# io-board-d-3.net
KiCad netlist of a schematic drawn in EAGLE
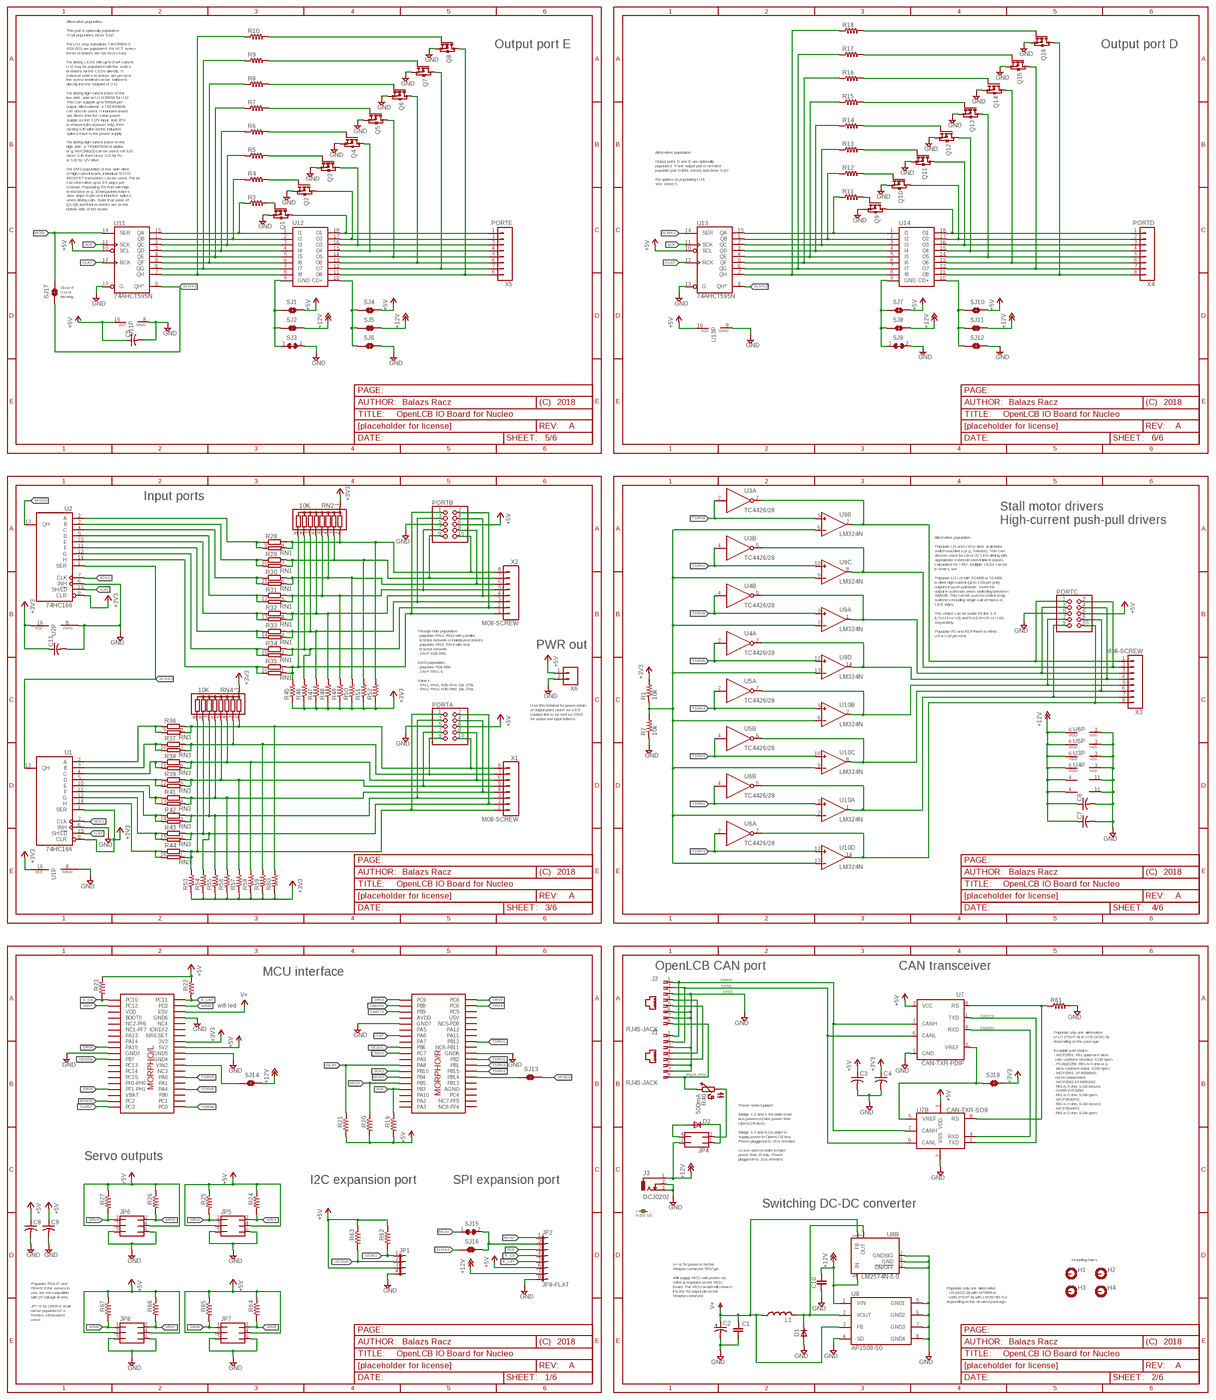
[diagram p0: schematic, sheet 1, overview]
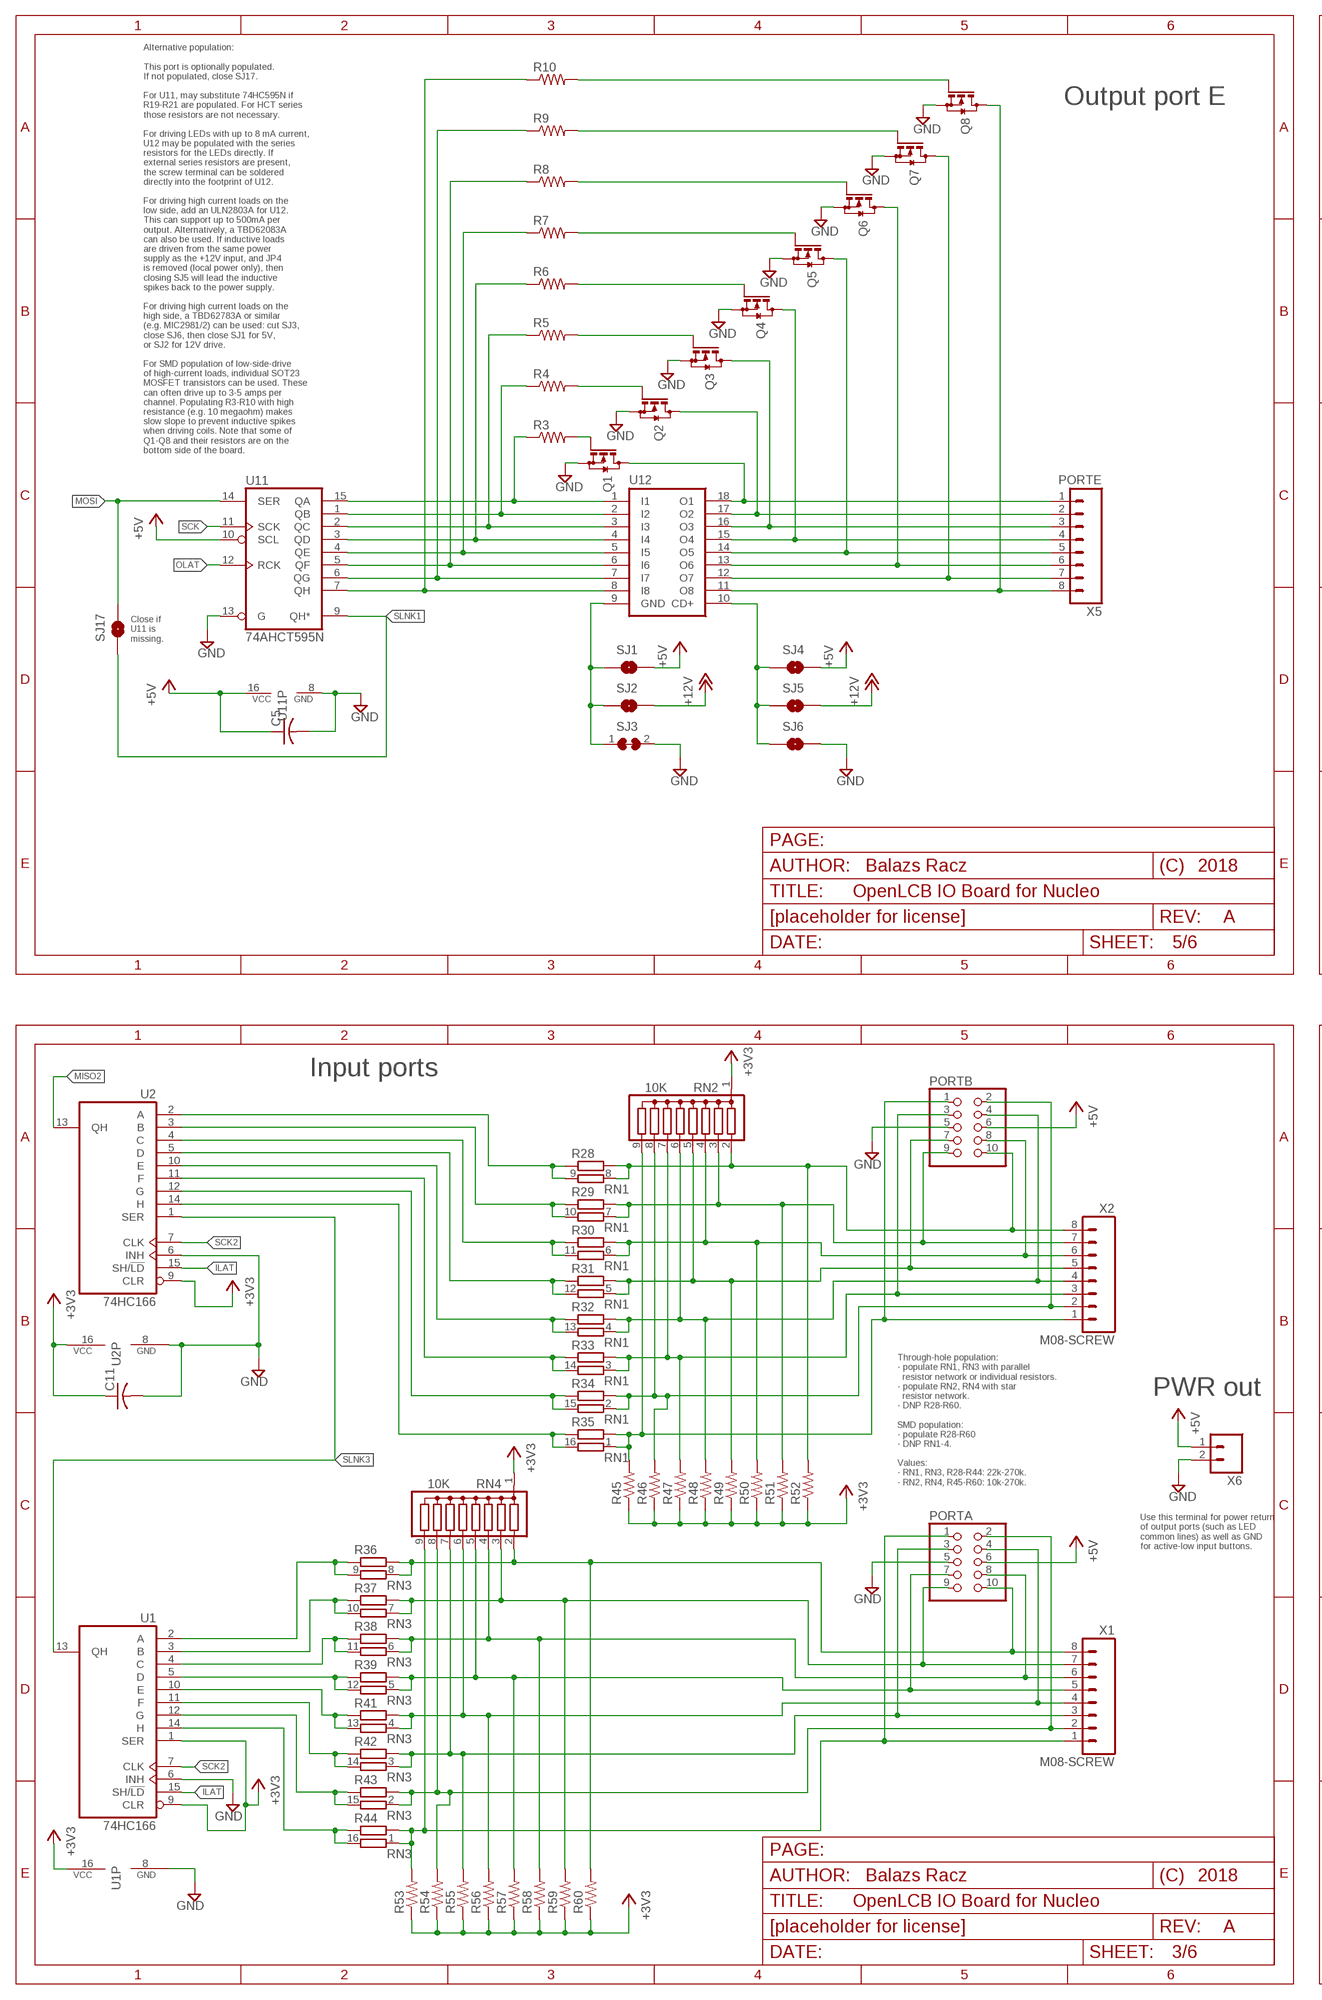
[diagram p1: schematic, sheet 1, part 1 of 4]
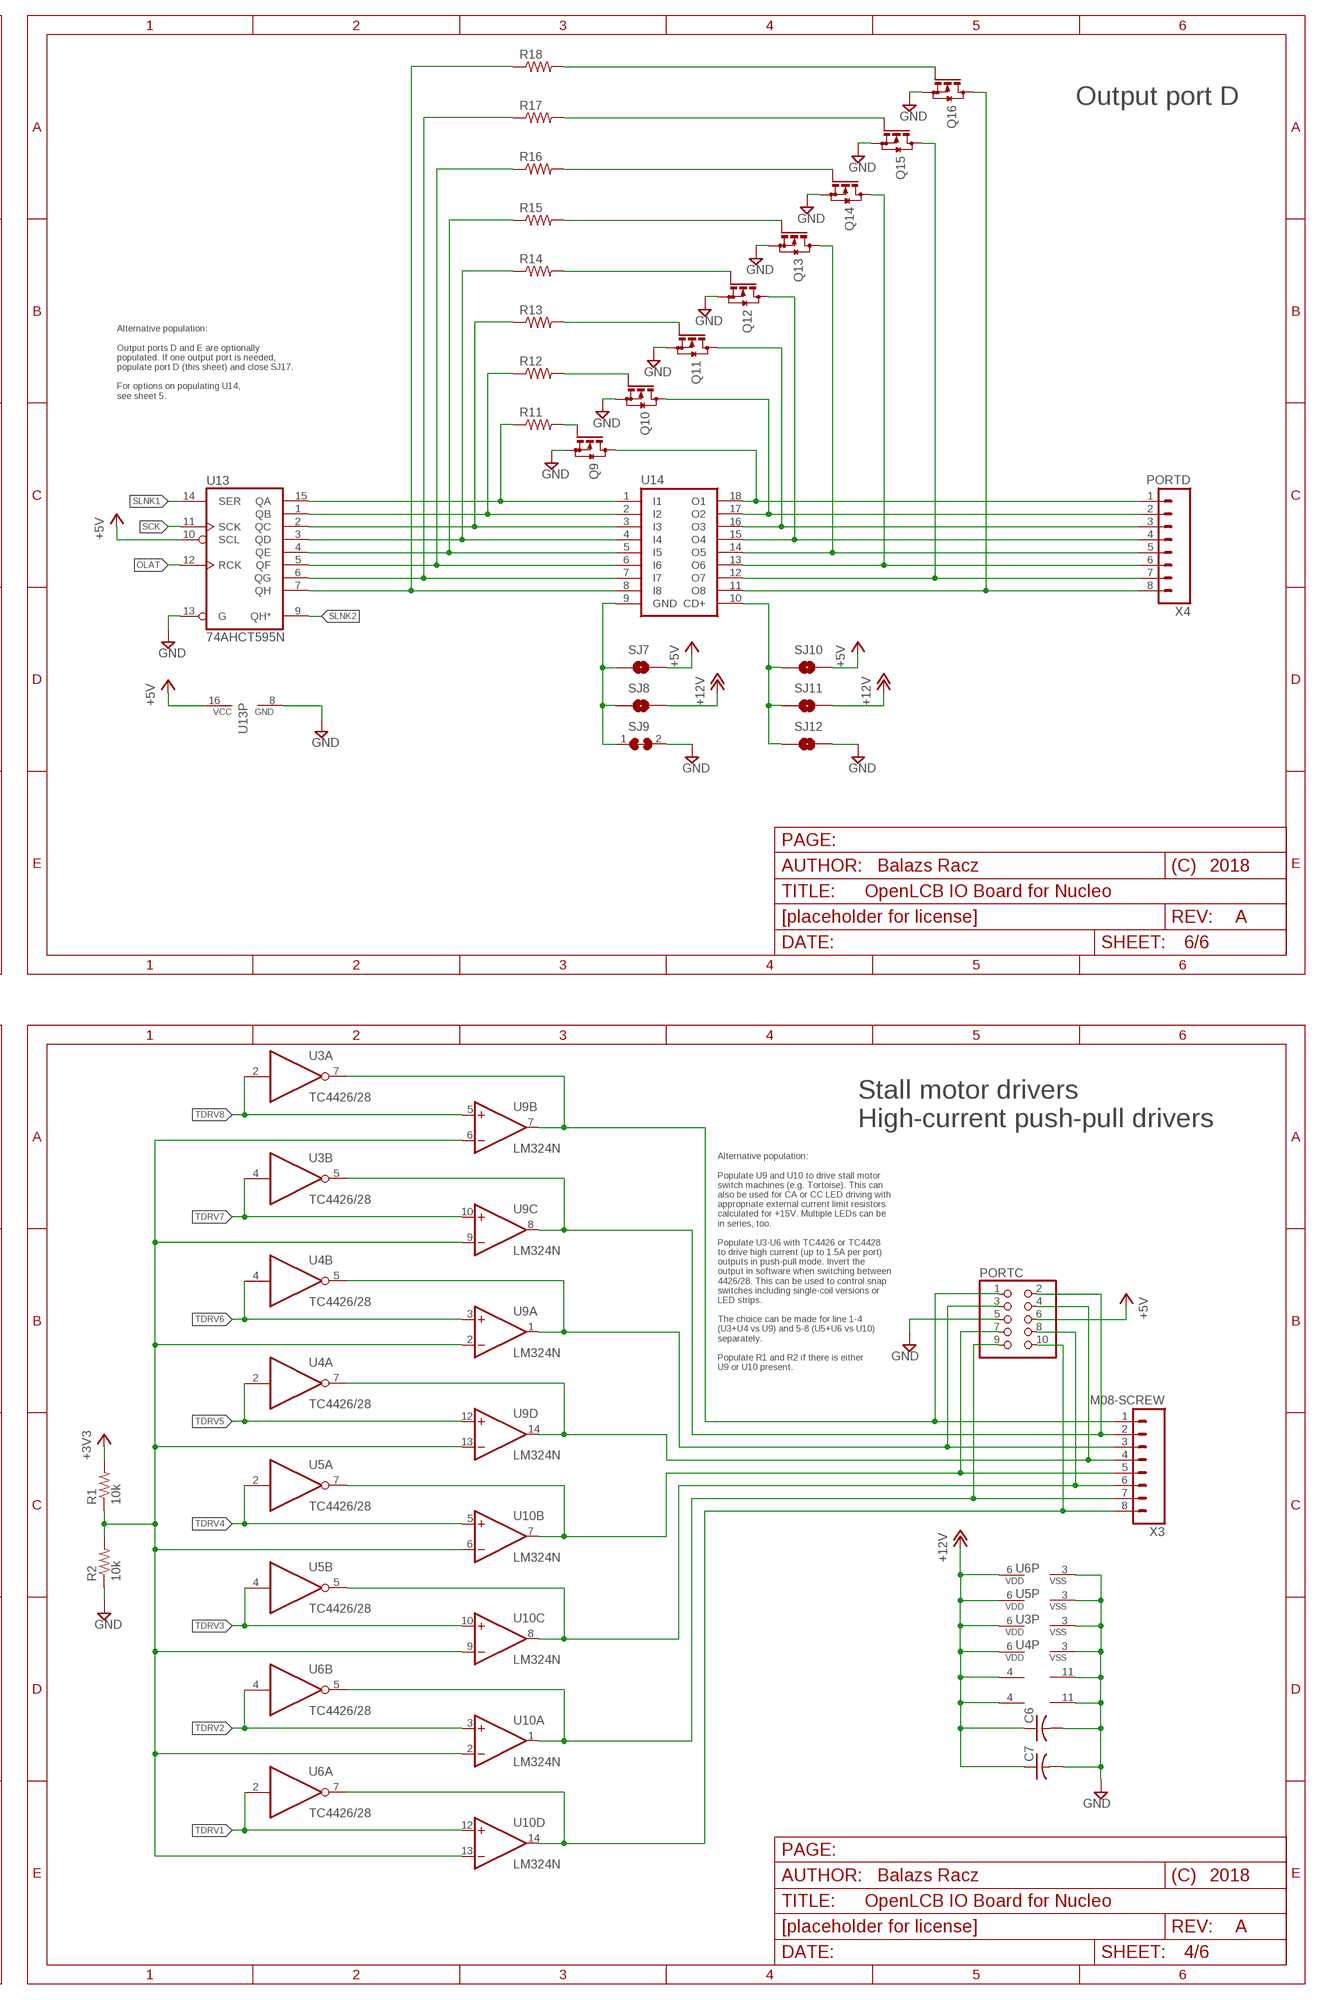
[diagram p2: schematic, sheet 1, part 2 of 4]
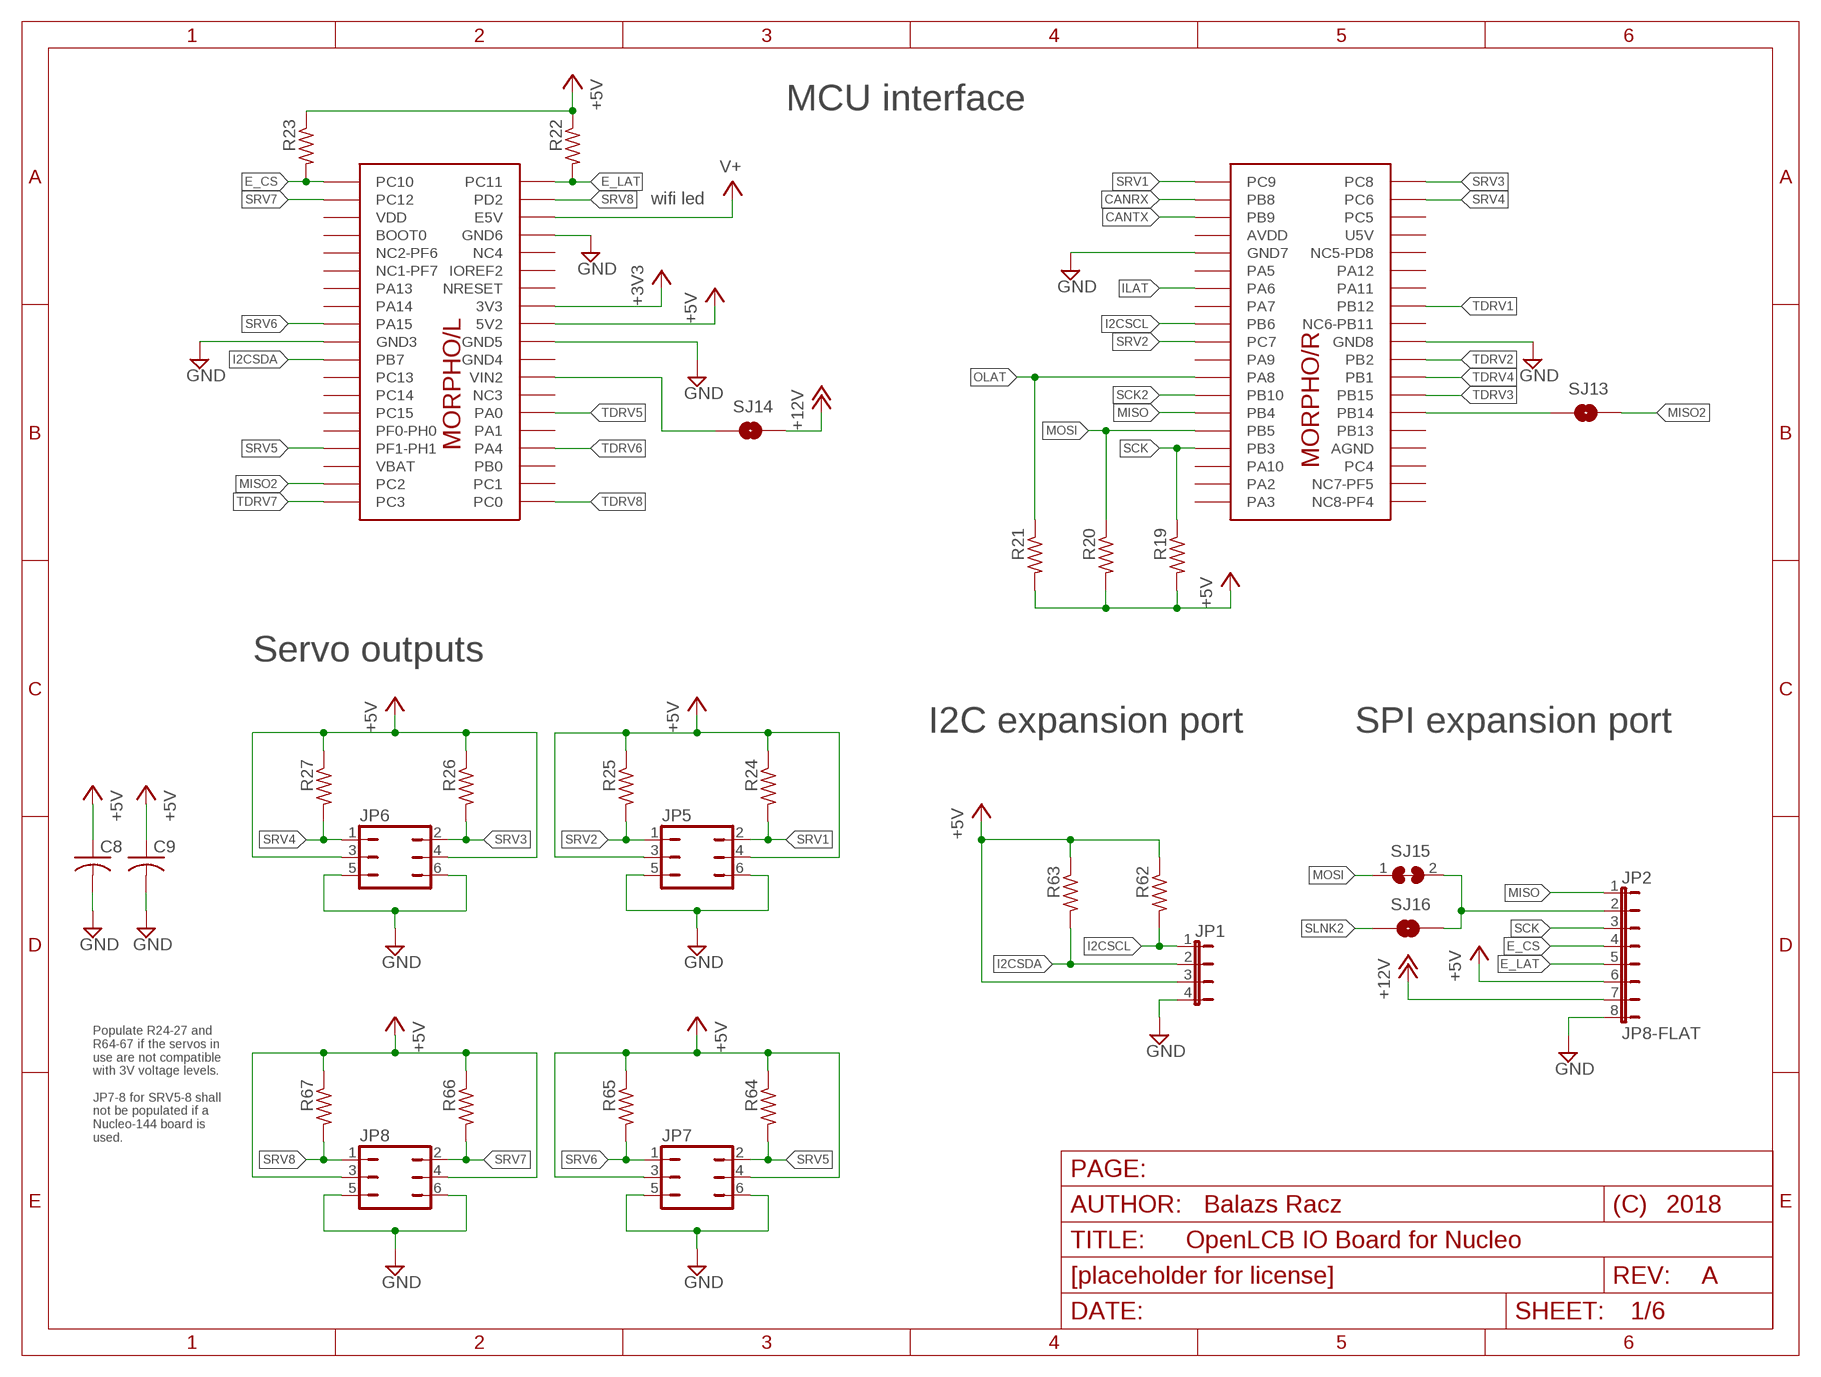
[diagram p3: schematic, sheet 1, part 3 of 4]
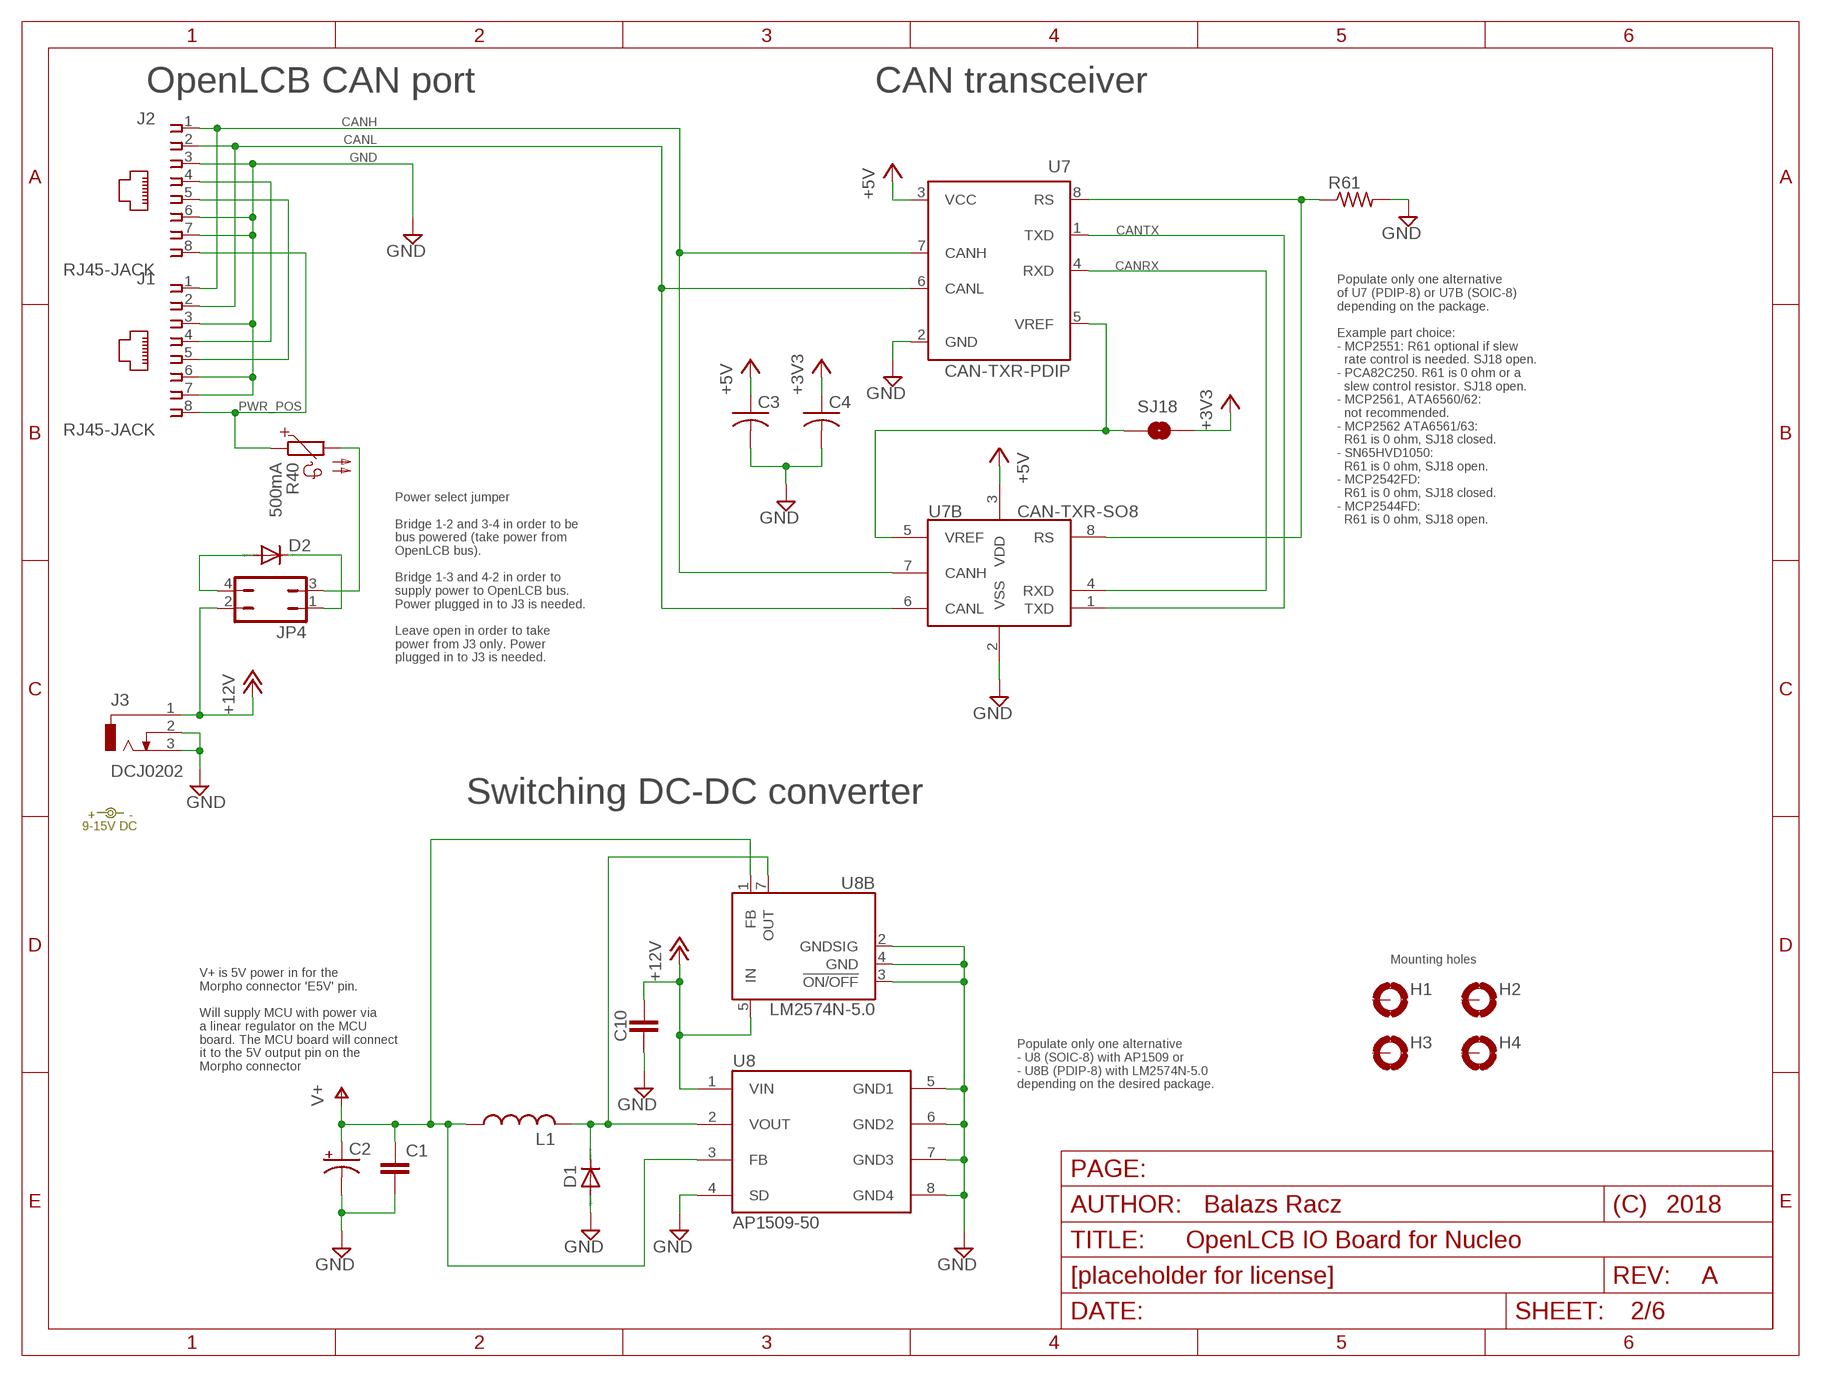
[diagram p4: schematic, sheet 1, part 4 of 4]

(export (version "E")
  (design (tool "Eeschema 10.0.6"))
  (components
    (comp (ref "+12V")
      (value "9-15V DC")
      (footprint "eagle-import:POWER_USAGE")
      (libsource (lib "eagle-import") (part "DOC-POWER_LABEL"))
    )
    (comp (ref "C1")
      (value "C-EUC1206")
      (footprint "eagle-import:C1206")
      (libsource (lib "eagle-import") (part "C-EUC1206"))
    )
    (comp (ref "C2")
      (value "CPOL-USE2.5-5")
      (footprint "eagle-import:E2,5-5")
      (libsource (lib "eagle-import") (part "CPOL-USE2.5-5"))
    )
    (comp (ref "C3")
      (value "C-USC0805")
      (footprint "eagle-import:C0805")
      (libsource (lib "eagle-import") (part "C-USC0805"))
    )
    (comp (ref "C4")
      (value "C-USC0805")
      (footprint "eagle-import:C0805")
      (libsource (lib "eagle-import") (part "C-USC0805"))
    )
    (comp (ref "C5")
      (value "C-USC0805")
      (footprint "eagle-import:C0805")
      (libsource (lib "eagle-import") (part "C-USC0805"))
    )
    (comp (ref "C6")
      (value "C-USC1206")
      (footprint "eagle-import:C1206")
      (libsource (lib "eagle-import") (part "C-USC1206"))
    )
    (comp (ref "C7")
      (value "C-USC1206")
      (footprint "eagle-import:C1206")
      (libsource (lib "eagle-import") (part "C-USC1206"))
    )
    (comp (ref "C8")
      (value "C-USC1206")
      (footprint "eagle-import:C1206")
      (libsource (lib "eagle-import") (part "C-USC1206"))
    )
    (comp (ref "C9")
      (value "C-USC1206")
      (footprint "eagle-import:C1206")
      (libsource (lib "eagle-import") (part "C-USC1206"))
    )
    (comp (ref "C10")
      (value "C-EUC1206")
      (footprint "eagle-import:C1206")
      (libsource (lib "eagle-import") (part "C-EUC1206"))
    )
    (comp (ref "C11")
      (value "C-USC0805")
      (footprint "eagle-import:C0805")
      (libsource (lib "eagle-import") (part "C-USC0805"))
    )
    (comp (ref "D1")
      (value "DIODE-DO41-7.6")
      (footprint "eagle-import:DO41-7.6")
      (libsource (lib "eagle-import") (part "DIODE-DO41-7.6"))
    )
    (comp (ref "D2")
      (value "DIODE-DO41-7.6")
      (footprint "eagle-import:DO41-7.6")
      (libsource (lib "eagle-import") (part "DIODE-DO41-7.6"))
    )
    (comp (ref "H1")
      (value "MOUNT-PAD-ROUND3.3")
      (footprint "eagle-import:3,3-PAD")
      (libsource (lib "eagle-import") (part "MOUNT-PAD-ROUND3.3"))
    )
    (comp (ref "H2")
      (value "MOUNT-PAD-ROUND3.3")
      (footprint "eagle-import:3,3-PAD")
      (libsource (lib "eagle-import") (part "MOUNT-PAD-ROUND3.3"))
    )
    (comp (ref "H3")
      (value "MOUNT-PAD-ROUND3.3")
      (footprint "eagle-import:3,3-PAD")
      (libsource (lib "eagle-import") (part "MOUNT-PAD-ROUND3.3"))
    )
    (comp (ref "H4")
      (value "MOUNT-PAD-ROUND3.3")
      (footprint "eagle-import:3,3-PAD")
      (libsource (lib "eagle-import") (part "MOUNT-PAD-ROUND3.3"))
    )
    (comp (ref "J1")
      (value "RJ45-JACK")
      (footprint "eagle-import:RJ45-PULSE-E5J88")
      (libsource (lib "eagle-import") (part "RJ45-JACKRJ45-PULSE-E5J00"))
    )
    (comp (ref "J2")
      (value "RJ45-JACK")
      (footprint "eagle-import:RJ45-PULSE-E5J88")
      (libsource (lib "eagle-import") (part "RJ45-JACKRJ45-PULSE-E5J00"))
    )
    (comp (ref "J3")
      (value "DCJ0202")
      (footprint "eagle-import:DCJ0202")
      (libsource (lib "eagle-import") (part "DCJ0202"))
    )
    (comp (ref "JP1")
      (value "JP4-FLAT")
      (footprint "eagle-import:JP4F")
      (libsource (lib "eagle-import") (part "JP4-FLAT"))
    )
    (comp (ref "JP2")
      (value "JP8-FLAT")
      (footprint "eagle-import:JP8F")
      (libsource (lib "eagle-import") (part "JP8-FLAT"))
    )
    (comp (ref "JP4")
      (value "JP2Q")
      (footprint "eagle-import:JP2Q")
      (libsource (lib "eagle-import") (part "JP2Q"))
    )
    (comp (ref "JP5")
      (value "JP3Q")
      (footprint "eagle-import:JP3Q")
      (libsource (lib "eagle-import") (part "JP3Q"))
    )
    (comp (ref "JP6")
      (value "JP3Q")
      (footprint "eagle-import:JP3Q")
      (libsource (lib "eagle-import") (part "JP3Q"))
    )
    (comp (ref "JP7")
      (value "JP3Q")
      (footprint "eagle-import:JP3Q")
      (libsource (lib "eagle-import") (part "JP3Q"))
    )
    (comp (ref "JP8")
      (value "JP3Q")
      (footprint "eagle-import:JP3Q")
      (libsource (lib "eagle-import") (part "JP3Q"))
    )
    (comp (ref "L1")
      (value "L-US")
      (footprint "eagle-import:L5-8,5")
      (libsource (lib "eagle-import") (part "L-US"))
    )
    (comp (ref "PORTA")
      (value "PINHD-2X5CN")
      (footprint "eagle-import:CON10M")
      (libsource (lib "eagle-import") (part "PINHD-2X5CN"))
    )
    (comp (ref "PORTB")
      (value "PINHD-2X5CN")
      (footprint "eagle-import:CON10M")
      (libsource (lib "eagle-import") (part "PINHD-2X5CN"))
    )
    (comp (ref "PORTC")
      (value "PINHD-2X5CN")
      (footprint "eagle-import:CON10M")
      (libsource (lib "eagle-import") (part "PINHD-2X5CN"))
    )
    (comp (ref "Q1")
      (value "BSS123")
      (footprint "eagle-import:SOT23")
      (libsource (lib "eagle-import") (part "BSS123"))
    )
    (comp (ref "Q2")
      (value "BSS123")
      (footprint "eagle-import:SOT23")
      (libsource (lib "eagle-import") (part "BSS123"))
    )
    (comp (ref "Q3")
      (value "BSS123")
      (footprint "eagle-import:SOT23")
      (libsource (lib "eagle-import") (part "BSS123"))
    )
    (comp (ref "Q4")
      (value "BSS123")
      (footprint "eagle-import:SOT23")
      (libsource (lib "eagle-import") (part "BSS123"))
    )
    (comp (ref "Q5")
      (value "BSS123")
      (footprint "eagle-import:SOT23")
      (libsource (lib "eagle-import") (part "BSS123"))
    )
    (comp (ref "Q6")
      (value "BSS123")
      (footprint "eagle-import:SOT23")
      (libsource (lib "eagle-import") (part "BSS123"))
    )
    (comp (ref "Q7")
      (value "BSS123")
      (footprint "eagle-import:SOT23")
      (libsource (lib "eagle-import") (part "BSS123"))
    )
    (comp (ref "Q8")
      (value "BSS123")
      (footprint "eagle-import:SOT23")
      (libsource (lib "eagle-import") (part "BSS123"))
    )
    (comp (ref "Q9")
      (value "BSS123")
      (footprint "eagle-import:SOT23")
      (libsource (lib "eagle-import") (part "BSS123"))
    )
    (comp (ref "Q10")
      (value "BSS123")
      (footprint "eagle-import:SOT23")
      (libsource (lib "eagle-import") (part "BSS123"))
    )
    (comp (ref "Q11")
      (value "BSS123")
      (footprint "eagle-import:SOT23")
      (libsource (lib "eagle-import") (part "BSS123"))
    )
    (comp (ref "Q12")
      (value "BSS123")
      (footprint "eagle-import:SOT23")
      (libsource (lib "eagle-import") (part "BSS123"))
    )
    (comp (ref "Q13")
      (value "BSS123")
      (footprint "eagle-import:SOT23")
      (libsource (lib "eagle-import") (part "BSS123"))
    )
    (comp (ref "Q14")
      (value "BSS123")
      (footprint "eagle-import:SOT23")
      (libsource (lib "eagle-import") (part "BSS123"))
    )
    (comp (ref "Q15")
      (value "BSS123")
      (footprint "eagle-import:SOT23")
      (libsource (lib "eagle-import") (part "BSS123"))
    )
    (comp (ref "Q16")
      (value "BSS123")
      (footprint "eagle-import:SOT23")
      (libsource (lib "eagle-import") (part "BSS123"))
    )
    (comp (ref "R1")
      (value "10k")
      (footprint "eagle-import:R0805")
      (libsource (lib "eagle-import") (part "R-US_R0805"))
    )
    (comp (ref "R2")
      (value "10k")
      (footprint "eagle-import:R0805")
      (libsource (lib "eagle-import") (part "R-US_R0805"))
    )
    (comp (ref "R3")
      (value "R-US_R0603")
      (footprint "eagle-import:R0603")
      (libsource (lib "eagle-import") (part "R-US_R0603"))
    )
    (comp (ref "R4")
      (value "R-US_R0603")
      (footprint "eagle-import:R0603")
      (libsource (lib "eagle-import") (part "R-US_R0603"))
    )
    (comp (ref "R5")
      (value "R-US_R0603")
      (footprint "eagle-import:R0603")
      (libsource (lib "eagle-import") (part "R-US_R0603"))
    )
    (comp (ref "R6")
      (value "R-US_R0603")
      (footprint "eagle-import:R0603")
      (libsource (lib "eagle-import") (part "R-US_R0603"))
    )
    (comp (ref "R7")
      (value "R-US_R0603")
      (footprint "eagle-import:R0603")
      (libsource (lib "eagle-import") (part "R-US_R0603"))
    )
    (comp (ref "R8")
      (value "R-US_R0603")
      (footprint "eagle-import:R0603")
      (libsource (lib "eagle-import") (part "R-US_R0603"))
    )
    (comp (ref "R9")
      (value "R-US_R0603")
      (footprint "eagle-import:R0603")
      (libsource (lib "eagle-import") (part "R-US_R0603"))
    )
    (comp (ref "R10")
      (value "R-US_R0603")
      (footprint "eagle-import:R0603")
      (libsource (lib "eagle-import") (part "R-US_R0603"))
    )
    (comp (ref "R11")
      (value "R-US_R0603")
      (footprint "eagle-import:R0603")
      (libsource (lib "eagle-import") (part "R-US_R0603"))
    )
    (comp (ref "R12")
      (value "R-US_R0603")
      (footprint "eagle-import:R0603")
      (libsource (lib "eagle-import") (part "R-US_R0603"))
    )
    (comp (ref "R13")
      (value "R-US_R0603")
      (footprint "eagle-import:R0603")
      (libsource (lib "eagle-import") (part "R-US_R0603"))
    )
    (comp (ref "R14")
      (value "R-US_R0603")
      (footprint "eagle-import:R0603")
      (libsource (lib "eagle-import") (part "R-US_R0603"))
    )
    (comp (ref "R15")
      (value "R-US_R0603")
      (footprint "eagle-import:R0603")
      (libsource (lib "eagle-import") (part "R-US_R0603"))
    )
    (comp (ref "R16")
      (value "R-US_R0603")
      (footprint "eagle-import:R0603")
      (libsource (lib "eagle-import") (part "R-US_R0603"))
    )
    (comp (ref "R17")
      (value "R-US_R0603")
      (footprint "eagle-import:R0603")
      (libsource (lib "eagle-import") (part "R-US_R0603"))
    )
    (comp (ref "R18")
      (value "R-US_R0603")
      (footprint "eagle-import:R0603")
      (libsource (lib "eagle-import") (part "R-US_R0603"))
    )
    (comp (ref "R19")
      (value "R-US_R0805")
      (footprint "eagle-import:R0805")
      (libsource (lib "eagle-import") (part "rcl_334_R-US_R0805"))
    )
    (comp (ref "R20")
      (value "R-US_R0805")
      (footprint "eagle-import:R0805")
      (libsource (lib "eagle-import") (part "rcl_334_R-US_R0805"))
    )
    (comp (ref "R21")
      (value "R-US_R0805")
      (footprint "eagle-import:R0805")
      (libsource (lib "eagle-import") (part "rcl_334_R-US_R0805"))
    )
    (comp (ref "R22")
      (value "R-US_R0805")
      (footprint "eagle-import:R0805")
      (libsource (lib "eagle-import") (part "rcl_334_R-US_R0805"))
    )
    (comp (ref "R23")
      (value "R-US_R0805")
      (footprint "eagle-import:R0805")
      (libsource (lib "eagle-import") (part "rcl_334_R-US_R0805"))
    )
    (comp (ref "R24")
      (value "R-US_R0805")
      (footprint "eagle-import:R0805")
      (libsource (lib "eagle-import") (part "rcl_334_R-US_R0805"))
    )
    (comp (ref "R25")
      (value "R-US_R0805")
      (footprint "eagle-import:R0805")
      (libsource (lib "eagle-import") (part "rcl_334_R-US_R0805"))
    )
    (comp (ref "R26")
      (value "R-US_R0805")
      (footprint "eagle-import:R0805")
      (libsource (lib "eagle-import") (part "rcl_334_R-US_R0805"))
    )
    (comp (ref "R27")
      (value "R-US_R0805")
      (footprint "eagle-import:R0805")
      (libsource (lib "eagle-import") (part "rcl_334_R-US_R0805"))
    )
    (comp (ref "R28")
      (value "R-EU_R0603")
      (footprint "eagle-import:R0603")
      (libsource (lib "eagle-import") (part "R-EU_R0603"))
    )
    (comp (ref "R29")
      (value "R-EU_R0603")
      (footprint "eagle-import:R0603")
      (libsource (lib "eagle-import") (part "R-EU_R0603"))
    )
    (comp (ref "R30")
      (value "R-EU_R0603")
      (footprint "eagle-import:R0603")
      (libsource (lib "eagle-import") (part "R-EU_R0603"))
    )
    (comp (ref "R31")
      (value "R-EU_R0603")
      (footprint "eagle-import:R0603")
      (libsource (lib "eagle-import") (part "R-EU_R0603"))
    )
    (comp (ref "R32")
      (value "R-EU_R0603")
      (footprint "eagle-import:R0603")
      (libsource (lib "eagle-import") (part "R-EU_R0603"))
    )
    (comp (ref "R33")
      (value "R-EU_R0603")
      (footprint "eagle-import:R0603")
      (libsource (lib "eagle-import") (part "R-EU_R0603"))
    )
    (comp (ref "R34")
      (value "R-EU_R0603")
      (footprint "eagle-import:R0603")
      (libsource (lib "eagle-import") (part "R-EU_R0603"))
    )
    (comp (ref "R35")
      (value "R-EU_R0603")
      (footprint "eagle-import:R0603")
      (libsource (lib "eagle-import") (part "R-EU_R0603"))
    )
    (comp (ref "R36")
      (value "R-EU_R0603")
      (footprint "eagle-import:R0603")
      (libsource (lib "eagle-import") (part "R-EU_R0603"))
    )
    (comp (ref "R37")
      (value "R-EU_R0603")
      (footprint "eagle-import:R0603")
      (libsource (lib "eagle-import") (part "R-EU_R0603"))
    )
    (comp (ref "R38")
      (value "R-EU_R0603")
      (footprint "eagle-import:R0603")
      (libsource (lib "eagle-import") (part "R-EU_R0603"))
    )
    (comp (ref "R39")
      (value "R-EU_R0603")
      (footprint "eagle-import:R0603")
      (libsource (lib "eagle-import") (part "R-EU_R0603"))
    )
    (comp (ref "R40")
      (value "500mA")
      (footprint "eagle-import:PTC1812")
      (libsource (lib "eagle-import") (part "PTC_1812"))
    )
    (comp (ref "R41")
      (value "R-EU_R0603")
      (footprint "eagle-import:R0603")
      (libsource (lib "eagle-import") (part "R-EU_R0603"))
    )
    (comp (ref "R42")
      (value "R-EU_R0603")
      (footprint "eagle-import:R0603")
      (libsource (lib "eagle-import") (part "R-EU_R0603"))
    )
    (comp (ref "R43")
      (value "R-EU_R0603")
      (footprint "eagle-import:R0603")
      (libsource (lib "eagle-import") (part "R-EU_R0603"))
    )
    (comp (ref "R44")
      (value "R-EU_R0603")
      (footprint "eagle-import:R0603")
      (libsource (lib "eagle-import") (part "R-EU_R0603"))
    )
    (comp (ref "R45")
      (value "R-US")
      (footprint "eagle-import:R0603")
      (libsource (lib "eagle-import") (part "R-US"))
    )
    (comp (ref "R46")
      (value "R-US")
      (footprint "eagle-import:R0603")
      (libsource (lib "eagle-import") (part "R-US"))
    )
    (comp (ref "R47")
      (value "R-US")
      (footprint "eagle-import:R0603")
      (libsource (lib "eagle-import") (part "R-US"))
    )
    (comp (ref "R48")
      (value "R-US")
      (footprint "eagle-import:R0603")
      (libsource (lib "eagle-import") (part "R-US"))
    )
    (comp (ref "R49")
      (value "R-US")
      (footprint "eagle-import:R0603")
      (libsource (lib "eagle-import") (part "R-US"))
    )
    (comp (ref "R50")
      (value "R-US")
      (footprint "eagle-import:R0603")
      (libsource (lib "eagle-import") (part "R-US"))
    )
    (comp (ref "R51")
      (value "R-US")
      (footprint "eagle-import:R0603")
      (libsource (lib "eagle-import") (part "R-US"))
    )
    (comp (ref "R52")
      (value "R-US")
      (footprint "eagle-import:R0603")
      (libsource (lib "eagle-import") (part "R-US"))
    )
    (comp (ref "R53")
      (value "R-US")
      (footprint "eagle-import:R0603")
      (libsource (lib "eagle-import") (part "R-US"))
    )
    (comp (ref "R54")
      (value "R-US")
      (footprint "eagle-import:R0603")
      (libsource (lib "eagle-import") (part "R-US"))
    )
    (comp (ref "R55")
      (value "R-US")
      (footprint "eagle-import:R0603")
      (libsource (lib "eagle-import") (part "R-US"))
    )
    (comp (ref "R56")
      (value "R-US")
      (footprint "eagle-import:R0603")
      (libsource (lib "eagle-import") (part "R-US"))
    )
    (comp (ref "R57")
      (value "R-US")
      (footprint "eagle-import:R0603")
      (libsource (lib "eagle-import") (part "R-US"))
    )
    (comp (ref "R58")
      (value "R-US")
      (footprint "eagle-import:R0603")
      (libsource (lib "eagle-import") (part "R-US"))
    )
    (comp (ref "R59")
      (value "R-US")
      (footprint "eagle-import:R0603")
      (libsource (lib "eagle-import") (part "R-US"))
    )
    (comp (ref "R60")
      (value "R-US")
      (footprint "eagle-import:R0603")
      (libsource (lib "eagle-import") (part "R-US"))
    )
    (comp (ref "R61")
      (value "R-US_R0805")
      (footprint "eagle-import:R0805")
      (libsource (lib "eagle-import") (part "rcl_334_R-US_R0805"))
    )
    (comp (ref "R62")
      (value "R-US_R0805")
      (footprint "eagle-import:R0805")
      (libsource (lib "eagle-import") (part "rcl_334_R-US_R0805"))
    )
    (comp (ref "R63")
      (value "R-US_R0805")
      (footprint "eagle-import:R0805")
      (libsource (lib "eagle-import") (part "rcl_334_R-US_R0805"))
    )
    (comp (ref "R64")
      (value "R-US_R0805")
      (footprint "eagle-import:R0805")
      (libsource (lib "eagle-import") (part "rcl_334_R-US_R0805"))
    )
    (comp (ref "R65")
      (value "R-US_R0805")
      (footprint "eagle-import:R0805")
      (libsource (lib "eagle-import") (part "rcl_334_R-US_R0805"))
    )
    (comp (ref "R66")
      (value "R-US_R0805")
      (footprint "eagle-import:R0805")
      (libsource (lib "eagle-import") (part "rcl_334_R-US_R0805"))
    )
    (comp (ref "R67")
      (value "R-US_R0805")
      (footprint "eagle-import:R0805")
      (libsource (lib "eagle-import") (part "rcl_334_R-US_R0805"))
    )
    (comp (ref "RN1")
      (value "8R-P")
      (footprint "eagle-import:DIL16")
      (libsource (lib "eagle-import") (part "8R-P"))
    )
    (comp (ref "RN2")
      (value "10K")
      (footprint "eagle-import:SIL9")
      (libsource (lib "eagle-import") (part "G08R"))
    )
    (comp (ref "RN3")
      (value "8R-P")
      (footprint "eagle-import:DIL16")
      (libsource (lib "eagle-import") (part "8R-P"))
    )
    (comp (ref "RN4")
      (value "10K")
      (footprint "eagle-import:SIL9")
      (libsource (lib "eagle-import") (part "G08R"))
    )
    (comp (ref "SJ1")
      (value "SJRND2")
      (footprint "eagle-import:SJ_RND2")
      (libsource (lib "eagle-import") (part "SJRND2"))
    )
    (comp (ref "SJ2")
      (value "SJRND2")
      (footprint "eagle-import:SJ_RND2")
      (libsource (lib "eagle-import") (part "SJRND2"))
    )
    (comp (ref "SJ3")
      (value "SJ-C")
      (footprint "eagle-import:SJW-C")
      (libsource (lib "eagle-import") (part "SJ-C"))
    )
    (comp (ref "SJ4")
      (value "SJRND2")
      (footprint "eagle-import:SJ_RND2")
      (libsource (lib "eagle-import") (part "SJRND2"))
    )
    (comp (ref "SJ5")
      (value "SJRND2")
      (footprint "eagle-import:SJ_RND2")
      (libsource (lib "eagle-import") (part "SJRND2"))
    )
    (comp (ref "SJ6")
      (value "SJRND2")
      (footprint "eagle-import:SJ_RND2")
      (libsource (lib "eagle-import") (part "SJRND2"))
    )
    (comp (ref "SJ7")
      (value "SJRND2")
      (footprint "eagle-import:SJ_RND2")
      (libsource (lib "eagle-import") (part "SJRND2"))
    )
    (comp (ref "SJ8")
      (value "SJRND2")
      (footprint "eagle-import:SJ_RND2")
      (libsource (lib "eagle-import") (part "SJRND2"))
    )
    (comp (ref "SJ9")
      (value "SJ-C")
      (footprint "eagle-import:SJW-C")
      (libsource (lib "eagle-import") (part "SJ-C"))
    )
    (comp (ref "SJ10")
      (value "SJRND2")
      (footprint "eagle-import:SJ_RND2")
      (libsource (lib "eagle-import") (part "SJRND2"))
    )
    (comp (ref "SJ11")
      (value "SJRND2")
      (footprint "eagle-import:SJ_RND2")
      (libsource (lib "eagle-import") (part "SJRND2"))
    )
    (comp (ref "SJ12")
      (value "SJRND2")
      (footprint "eagle-import:SJ_RND2")
      (libsource (lib "eagle-import") (part "SJRND2"))
    )
    (comp (ref "SJ13")
      (value "SJRND2")
      (footprint "eagle-import:SJ_RND2")
      (libsource (lib "eagle-import") (part "SJRND2"))
    )
    (comp (ref "SJ14")
      (value "SJRND2")
      (footprint "eagle-import:SJ_RND2")
      (libsource (lib "eagle-import") (part "SJRND2"))
    )
    (comp (ref "SJ15")
      (value "SJ-C")
      (footprint "eagle-import:SJW-C")
      (libsource (lib "eagle-import") (part "SJ-C"))
    )
    (comp (ref "SJ16")
      (value "SJRND2")
      (footprint "eagle-import:SJ_RND2")
      (libsource (lib "eagle-import") (part "SJRND2"))
    )
    (comp (ref "SJ17")
      (value "SJRND2")
      (footprint "eagle-import:SJ_RND2")
      (libsource (lib "eagle-import") (part "SJRND2"))
    )
    (comp (ref "SJ18")
      (value "SJRND2")
      (footprint "eagle-import:SJ_RND2")
      (libsource (lib "eagle-import") (part "SJRND2"))
    )
    (comp (ref "U$1")
      (value "NUCLEO_64_GENERIC")
      (footprint "eagle-import:NUCLEO_BRD_BASE64")
      (libsource (lib "eagle-import") (part "NUCLEO_64_GENERIC"))
    )
    (comp (ref "U1")
      (value "74HC166")
      (footprint "eagle-import:DIL16")
      (libsource (lib "eagle-import") (part "74166N"))
    )
    (comp (ref "U2")
      (value "74HC166")
      (footprint "eagle-import:DIL16")
      (libsource (lib "eagle-import") (part "74166N"))
    )
    (comp (ref "U3")
      (value "TC4426/28")
      (footprint "eagle-import:DIL08-LONG")
      (libsource (lib "eagle-import") (part "TC4426APDIP"))
    )
    (comp (ref "U4")
      (value "TC4426/28")
      (footprint "eagle-import:DIL08-LONG")
      (libsource (lib "eagle-import") (part "TC4426APDIP"))
    )
    (comp (ref "U5")
      (value "TC4426/28")
      (footprint "eagle-import:DIL08-LONG")
      (libsource (lib "eagle-import") (part "TC4426APDIP"))
    )
    (comp (ref "U6")
      (value "TC4426/28")
      (footprint "eagle-import:DIL08-LONG")
      (libsource (lib "eagle-import") (part "TC4426APDIP"))
    )
    (comp (ref "U7")
      (value "CAN-TXR-PDIP")
      (footprint "eagle-import:DIL08")
      (libsource (lib "eagle-import") (part "PCA82C250"))
    )
    (comp (ref "U7B")
      (value "CAN-TXR-SO8")
      (footprint "eagle-import:SO-08")
      (libsource (lib "eagle-import") (part "MCP2551-SN"))
    )
    (comp (ref "U8")
      (value "AP1509-50")
      (footprint "eagle-import:SO-08")
      (libsource (lib "eagle-import") (part "AP1509"))
    )
    (comp (ref "U8B")
      (value "LM2574N-5.0")
      (footprint "eagle-import:DIL08")
      (libsource (lib "eagle-import") (part "LM2574?-N5.0"))
    )
    (comp (ref "U9")
      (value "LM324N")
      (footprint "eagle-import:DIL14")
      (libsource (lib "eagle-import") (part "LM324N"))
    )
    (comp (ref "U10")
      (value "LM324N")
      (footprint "eagle-import:DIL14")
      (libsource (lib "eagle-import") (part "LM324N"))
    )
    (comp (ref "U11")
      (value "74AHCT595N")
      (footprint "eagle-import:DIL16")
      (libsource (lib "eagle-import") (part "74595NHCT"))
    )
    (comp (ref "U12")
      (value "ULN2803A")
      (footprint "eagle-import:DIL18-THIN")
      (libsource (lib "eagle-import") (part "ULN2803A"))
    )
    (comp (ref "U13")
      (value "74AHCT595N")
      (footprint "eagle-import:DIL16")
      (libsource (lib "eagle-import") (part "74595NHCT"))
    )
    (comp (ref "U14")
      (value "ULN2803A")
      (footprint "eagle-import:DIL18-THIN")
      (libsource (lib "eagle-import") (part "ULN2803A"))
    )
    (comp (ref "X1")
      (value "M08-SCREW")
      (footprint "eagle-import:1X08_TERMINAL")
      (libsource (lib "eagle-import") (part "M08-SCREW"))
    )
    (comp (ref "X2")
      (value "M08-SCREW")
      (footprint "eagle-import:1X08_TERMINAL")
      (libsource (lib "eagle-import") (part "M08-SCREW"))
    )
    (comp (ref "X3")
      (value "M08-SCREW")
      (footprint "eagle-import:1X08_TERMINAL")
      (libsource (lib "eagle-import") (part "M08-SCREW"))
    )
    (comp (ref "X4")
      (value "PORTD")
      (footprint "eagle-import:1X08_TERMINAL")
      (libsource (lib "eagle-import") (part "M08-SCREW"))
    )
    (comp (ref "X5")
      (value "PORTE")
      (footprint "eagle-import:1X08_TERMINAL")
      (libsource (lib "eagle-import") (part "M08-SCREW"))
    )
    (comp (ref "X6")
      (value "CONNECTOR-M023.5MM-LOCK")
      (footprint "eagle-import:SCREWTERMINAL-3.5MM-2_LOCK")
      (libsource (lib "eagle-import") (part "CONNECTOR-M023.5MM-LOCK"))
    )
  )
  (nets
    (net (code "1") (name "+3V3") (class "Default")
      (node (ref "C11") (pin "1") (pinfunction "1_1") (pintype "passive"))
      (node (ref "C4") (pin "1") (pinfunction "1_1") (pintype "passive"))
      (node (ref "R1") (pin "2") (pinfunction "2_2") (pintype "passive"))
      (node (ref "R45") (pin "1") (pinfunction "1_1") (pintype "passive"))
      (node (ref "R46") (pin "1") (pinfunction "1_1") (pintype "passive"))
      (node (ref "R47") (pin "1") (pinfunction "1_1") (pintype "passive"))
      (node (ref "R48") (pin "1") (pinfunction "1_1") (pintype "passive"))
      (node (ref "R49") (pin "1") (pinfunction "1_1") (pintype "passive"))
      (node (ref "R50") (pin "1") (pinfunction "1_1") (pintype "passive"))
      (node (ref "R51") (pin "1") (pinfunction "1_1") (pintype "passive"))
      (node (ref "R52") (pin "1") (pinfunction "1_1") (pintype "passive"))
      (node (ref "R53") (pin "1") (pinfunction "1_1") (pintype "passive"))
      (node (ref "R54") (pin "1") (pinfunction "1_1") (pintype "passive"))
      (node (ref "R55") (pin "1") (pinfunction "1_1") (pintype "passive"))
      (node (ref "R56") (pin "1") (pinfunction "1_1") (pintype "passive"))
      (node (ref "R57") (pin "1") (pinfunction "1_1") (pintype "passive"))
      (node (ref "R58") (pin "1") (pinfunction "1_1") (pintype "passive"))
      (node (ref "R59") (pin "1") (pinfunction "1_1") (pintype "passive"))
      (node (ref "R60") (pin "1") (pinfunction "1_1") (pintype "passive"))
      (node (ref "RN2") (pin "1") (pinfunction "1_1") (pintype "passive"))
      (node (ref "RN4") (pin "1") (pinfunction "1_1") (pintype "passive"))
      (node (ref "SJ18") (pin "P$1") (pinfunction "1_P$1") (pintype "passive"))
      (node (ref "U$1") (pin "3V3") (pinfunction "3V3_3V3") (pintype "power_in"))
      (node (ref "U1") (pin "1") (pinfunction "SER_1") (pintype "input"))
      (node (ref "U1") (pin "16") (pinfunction "VCC_16") (pintype "power_in"))
      (node (ref "U1") (pin "9") (pinfunction "CLR_9") (pintype "input"))
      (node (ref "U2") (pin "16") (pinfunction "VCC_16") (pintype "power_in"))
      (node (ref "U2") (pin "9") (pinfunction "CLR_9") (pintype "input"))
    )
    (net (code "2") (name "+5V") (class "Default")
      (node (ref "C3") (pin "1") (pinfunction "1_1") (pintype "passive"))
      (node (ref "C5") (pin "1") (pinfunction "1_1") (pintype "passive"))
      (node (ref "C8") (pin "1") (pinfunction "1_1") (pintype "passive"))
      (node (ref "C9") (pin "1") (pinfunction "1_1") (pintype "passive"))
      (node (ref "JP1") (pin "3") (pinfunction "3_3") (pintype "passive"))
      (node (ref "JP2") (pin "6") (pinfunction "6_6") (pintype "passive"))
      (node (ref "JP5") (pin "3") (pinfunction "3_3") (pintype "passive"))
      (node (ref "JP5") (pin "4") (pinfunction "4_4") (pintype "passive"))
      (node (ref "JP6") (pin "3") (pinfunction "3_3") (pintype "passive"))
      (node (ref "JP6") (pin "4") (pinfunction "4_4") (pintype "passive"))
      (node (ref "JP7") (pin "3") (pinfunction "3_3") (pintype "passive"))
      (node (ref "JP7") (pin "4") (pinfunction "4_4") (pintype "passive"))
      (node (ref "JP8") (pin "3") (pinfunction "3_3") (pintype "passive"))
      (node (ref "JP8") (pin "4") (pinfunction "4_4") (pintype "passive"))
      (node (ref "PORTA") (pin "6") (pinfunction "6_6") (pintype "passive"))
      (node (ref "PORTB") (pin "6") (pinfunction "6_6") (pintype "passive"))
      (node (ref "PORTC") (pin "6") (pinfunction "6_6") (pintype "passive"))
      (node (ref "R19") (pin "2") (pinfunction "2_2") (pintype "passive"))
      (node (ref "R20") (pin "2") (pinfunction "2_2") (pintype "passive"))
      (node (ref "R21") (pin "2") (pinfunction "2_2") (pintype "passive"))
      (node (ref "R22") (pin "1") (pinfunction "1_1") (pintype "passive"))
      (node (ref "R23") (pin "1") (pinfunction "1_1") (pintype "passive"))
      (node (ref "R24") (pin "1") (pinfunction "1_1") (pintype "passive"))
      (node (ref "R25") (pin "1") (pinfunction "1_1") (pintype "passive"))
      (node (ref "R26") (pin "1") (pinfunction "1_1") (pintype "passive"))
      (node (ref "R27") (pin "1") (pinfunction "1_1") (pintype "passive"))
      (node (ref "R62") (pin "1") (pinfunction "1_1") (pintype "passive"))
      (node (ref "R63") (pin "1") (pinfunction "1_1") (pintype "passive"))
      (node (ref "R64") (pin "1") (pinfunction "1_1") (pintype "passive"))
      (node (ref "R65") (pin "1") (pinfunction "1_1") (pintype "passive"))
      (node (ref "R66") (pin "1") (pinfunction "1_1") (pintype "passive"))
      (node (ref "R67") (pin "1") (pinfunction "1_1") (pintype "passive"))
      (node (ref "SJ1") (pin "P$2") (pinfunction "2_P$2") (pintype "passive"))
      (node (ref "SJ10") (pin "P$2") (pinfunction "2_P$2") (pintype "passive"))
      (node (ref "SJ4") (pin "P$2") (pinfunction "2_P$2") (pintype "passive"))
      (node (ref "SJ7") (pin "P$2") (pinfunction "2_P$2") (pintype "passive"))
      (node (ref "U$1") (pin "5V2") (pinfunction "5V2_5V2") (pintype "power_in"))
      (node (ref "U11") (pin "10") (pinfunction "SCL_10") (pintype "input"))
      (node (ref "U11") (pin "16") (pinfunction "VCC_16") (pintype "power_in"))
      (node (ref "U13") (pin "10") (pinfunction "SCL_10") (pintype "input"))
      (node (ref "U13") (pin "16") (pinfunction "VCC_16") (pintype "power_in"))
      (node (ref "U7") (pin "3") (pinfunction "VCC_3") (pintype "power_in"))
      (node (ref "U7B") (pin "3") (pinfunction "VDD_3") (pintype "power_in"))
      (node (ref "X6") (pin "1") (pinfunction "1_1") (pintype "passive"))
    )
    (net (code "3") (name "+12V") (class "Default")
      (node (ref "C10") (pin "1") (pinfunction "1_1") (pintype "passive"))
      (node (ref "C6") (pin "1") (pinfunction "1_1") (pintype "passive"))
      (node (ref "C7") (pin "1") (pinfunction "1_1") (pintype "passive"))
      (node (ref "J3") (pin "1") (pinfunction "1_1") (pintype "passive"))
      (node (ref "JP2") (pin "7") (pinfunction "7_7") (pintype "passive"))
      (node (ref "JP4") (pin "2") (pinfunction "2_2") (pintype "passive"))
      (node (ref "SJ11") (pin "P$2") (pinfunction "2_P$2") (pintype "passive"))
      (node (ref "SJ14") (pin "P$2") (pinfunction "2_P$2") (pintype "passive"))
      (node (ref "SJ2") (pin "P$2") (pinfunction "2_P$2") (pintype "passive"))
      (node (ref "SJ5") (pin "P$2") (pinfunction "2_P$2") (pintype "passive"))
      (node (ref "SJ8") (pin "P$2") (pinfunction "2_P$2") (pintype "passive"))
      (node (ref "U10") (pin "4") (pinfunction "V+_4") (pintype "power_in"))
      (node (ref "U3") (pin "6") (pinfunction "VDD_6") (pintype "power_in"))
      (node (ref "U4") (pin "6") (pinfunction "VDD_6") (pintype "power_in"))
      (node (ref "U5") (pin "6") (pinfunction "VDD_6") (pintype "power_in"))
      (node (ref "U6") (pin "6") (pinfunction "VDD_6") (pintype "power_in"))
      (node (ref "U8") (pin "1") (pinfunction "VIN_1") (pintype "bidirectional"))
      (node (ref "U8B") (pin "5") (pinfunction "IN_5") (pintype "input"))
      (node (ref "U9") (pin "4") (pinfunction "V+_4") (pintype "power_in"))
    )
    (net (code "4") (name "/AGND") (class "Default")
      (node (ref "U$1") (pin "AGND") (pinfunction "AGND_AGND") (pintype "power_in"))
    )
    (net (code "5") (name "/AVDD") (class "Default")
      (node (ref "U$1") (pin "AVDD") (pinfunction "AVDD_AVDD") (pintype "power_in"))
    )
    (net (code "6") (name "/CANH") (class "Default")
      (node (ref "J1") (pin "1") (pinfunction "1_1") (pintype "passive"))
      (node (ref "J2") (pin "1") (pinfunction "1_1") (pintype "passive"))
      (node (ref "U7") (pin "7") (pinfunction "CANH_7") (pintype "bidirectional"))
      (node (ref "U7B") (pin "7") (pinfunction "CANH_7") (pintype "bidirectional"))
    )
    (net (code "7") (name "/CANL") (class "Default")
      (node (ref "J1") (pin "2") (pinfunction "2_2") (pintype "passive"))
      (node (ref "J2") (pin "2") (pinfunction "2_2") (pintype "passive"))
      (node (ref "U7") (pin "6") (pinfunction "CANL_6") (pintype "bidirectional"))
      (node (ref "U7B") (pin "6") (pinfunction "CANL_6") (pintype "bidirectional"))
    )
    (net (code "8") (name "/GND4") (class "Default")
      (node (ref "U$1") (pin "GND4") (pinfunction "GND4_GND4") (pintype "power_in"))
    )
    (net (code "9") (name "/PWR_POS") (class "Default")
      (node (ref "J1") (pin "8") (pinfunction "8_8") (pintype "passive"))
      (node (ref "J2") (pin "8") (pinfunction "8_8") (pintype "passive"))
      (node (ref "R40") (pin "1") (pinfunction "1_1") (pintype "passive"))
    )
    (net (code "10") (name "/U5V") (class "Default")
      (node (ref "U$1") (pin "U5V") (pinfunction "U5V_U5V") (pintype "power_in"))
    )
    (net (code "11") (name "/VBAT") (class "Default")
      (node (ref "U$1") (pin "VBAT") (pinfunction "VBAT_VBAT") (pintype "power_in"))
    )
    (net (code "12") (name "/VDD") (class "Default")
      (node (ref "U$1") (pin "VDD") (pinfunction "VDD_VDD") (pintype "power_in"))
    )
    (net (code "13") (name "CANRX") (class "Default")
      (node (ref "U$1") (pin "PB8") (pinfunction "PB8_PB8") (pintype "bidirectional"))
      (node (ref "U7") (pin "4") (pinfunction "RXD_4") (pintype "output"))
      (node (ref "U7B") (pin "4") (pinfunction "RXD_4") (pintype "bidirectional"))
    )
    (net (code "14") (name "CANTX") (class "Default")
      (node (ref "U$1") (pin "PB9") (pinfunction "PB9_PB9") (pintype "bidirectional"))
      (node (ref "U7") (pin "1") (pinfunction "TXD_1") (pintype "input"))
      (node (ref "U7B") (pin "1") (pinfunction "TXD_1") (pintype "bidirectional"))
    )
    (net (code "15") (name "E_CS") (class "Default")
      (node (ref "JP2") (pin "4") (pinfunction "4_4") (pintype "passive"))
      (node (ref "R23") (pin "2") (pinfunction "2_2") (pintype "passive"))
      (node (ref "U$1") (pin "PC10") (pinfunction "PC10_PC10") (pintype "bidirectional"))
    )
    (net (code "16") (name "E_LAT") (class "Default")
      (node (ref "JP2") (pin "5") (pinfunction "5_5") (pintype "passive"))
      (node (ref "R22") (pin "2") (pinfunction "2_2") (pintype "passive"))
      (node (ref "U$1") (pin "PC11") (pinfunction "PC11_PC11") (pintype "bidirectional"))
    )
    (net (code "17") (name "GND") (class "Default")
      (node (ref "C1") (pin "2") (pinfunction "2_2") (pintype "passive"))
      (node (ref "C10") (pin "2") (pinfunction "2_2") (pintype "passive"))
      (node (ref "C11") (pin "2") (pinfunction "2_2") (pintype "passive"))
      (node (ref "C2") (pin "-") (pinfunction "-_-") (pintype "passive"))
      (node (ref "C3") (pin "2") (pinfunction "2_2") (pintype "passive"))
      (node (ref "C4") (pin "2") (pinfunction "2_2") (pintype "passive"))
      (node (ref "C5") (pin "2") (pinfunction "2_2") (pintype "passive"))
      (node (ref "C6") (pin "2") (pinfunction "2_2") (pintype "passive"))
      (node (ref "C7") (pin "2") (pinfunction "2_2") (pintype "passive"))
      (node (ref "C8") (pin "2") (pinfunction "2_2") (pintype "passive"))
      (node (ref "C9") (pin "2") (pinfunction "2_2") (pintype "passive"))
      (node (ref "D1") (pin "A") (pinfunction "A_A") (pintype "passive"))
      (node (ref "J1") (pin "3") (pinfunction "3_3") (pintype "passive"))
      (node (ref "J1") (pin "6") (pinfunction "6_6") (pintype "passive"))
      (node (ref "J1") (pin "7") (pinfunction "7_7") (pintype "passive"))
      (node (ref "J2") (pin "3") (pinfunction "3_3") (pintype "passive"))
      (node (ref "J2") (pin "6") (pinfunction "6_6") (pintype "passive"))
      (node (ref "J2") (pin "7") (pinfunction "7_7") (pintype "passive"))
      (node (ref "J3") (pin "2") (pinfunction "2_2") (pintype "passive"))
      (node (ref "J3") (pin "3") (pinfunction "3_3") (pintype "passive"))
      (node (ref "JP1") (pin "4") (pinfunction "4_4") (pintype "passive"))
      (node (ref "JP2") (pin "8") (pinfunction "8_8") (pintype "passive"))
      (node (ref "JP5") (pin "5") (pinfunction "5_5") (pintype "passive"))
      (node (ref "JP5") (pin "6") (pinfunction "6_6") (pintype "passive"))
      (node (ref "JP6") (pin "5") (pinfunction "5_5") (pintype "passive"))
      (node (ref "JP6") (pin "6") (pinfunction "6_6") (pintype "passive"))
      (node (ref "JP7") (pin "5") (pinfunction "5_5") (pintype "passive"))
      (node (ref "JP7") (pin "6") (pinfunction "6_6") (pintype "passive"))
      (node (ref "JP8") (pin "5") (pinfunction "5_5") (pintype "passive"))
      (node (ref "JP8") (pin "6") (pinfunction "6_6") (pintype "passive"))
      (node (ref "PORTA") (pin "5") (pinfunction "5_5") (pintype "passive"))
      (node (ref "PORTB") (pin "5") (pinfunction "5_5") (pintype "passive"))
      (node (ref "PORTC") (pin "5") (pinfunction "5_5") (pintype "passive"))
      (node (ref "Q1") (pin "2") (pinfunction "S_2") (pintype "passive"))
      (node (ref "Q10") (pin "2") (pinfunction "S_2") (pintype "passive"))
      (node (ref "Q11") (pin "2") (pinfunction "S_2") (pintype "passive"))
      (node (ref "Q12") (pin "2") (pinfunction "S_2") (pintype "passive"))
      (node (ref "Q13") (pin "2") (pinfunction "S_2") (pintype "passive"))
      (node (ref "Q14") (pin "2") (pinfunction "S_2") (pintype "passive"))
      (node (ref "Q15") (pin "2") (pinfunction "S_2") (pintype "passive"))
      (node (ref "Q16") (pin "2") (pinfunction "S_2") (pintype "passive"))
      (node (ref "Q2") (pin "2") (pinfunction "S_2") (pintype "passive"))
      (node (ref "Q3") (pin "2") (pinfunction "S_2") (pintype "passive"))
      (node (ref "Q4") (pin "2") (pinfunction "S_2") (pintype "passive"))
      (node (ref "Q5") (pin "2") (pinfunction "S_2") (pintype "passive"))
      (node (ref "Q6") (pin "2") (pinfunction "S_2") (pintype "passive"))
      (node (ref "Q7") (pin "2") (pinfunction "S_2") (pintype "passive"))
      (node (ref "Q8") (pin "2") (pinfunction "S_2") (pintype "passive"))
      (node (ref "Q9") (pin "2") (pinfunction "S_2") (pintype "passive"))
      (node (ref "R2") (pin "1") (pinfunction "1_1") (pintype "passive"))
      (node (ref "R61") (pin "2") (pinfunction "2_2") (pintype "passive"))
      (node (ref "SJ12") (pin "P$2") (pinfunction "2_P$2") (pintype "passive"))
      (node (ref "SJ3") (pin "2") (pinfunction "2_2") (pintype "passive"))
      (node (ref "SJ6") (pin "P$2") (pinfunction "2_P$2") (pintype "passive"))
      (node (ref "SJ9") (pin "2") (pinfunction "2_2") (pintype "passive"))
      (node (ref "U$1") (pin "GND3") (pinfunction "GND3_GND3") (pintype "power_in"))
      (node (ref "U$1") (pin "GND5") (pinfunction "GND5_GND5") (pintype "power_in"))
      (node (ref "U$1") (pin "GND6") (pinfunction "GND6_GND6") (pintype "power_in"))
      (node (ref "U$1") (pin "GND7") (pinfunction "GND7_GND7") (pintype "power_in"))
      (node (ref "U$1") (pin "GND8") (pinfunction "GND8_GND8") (pintype "power_in"))
      (node (ref "U1") (pin "6") (pinfunction "INH_6") (pintype "input"))
      (node (ref "U1") (pin "8") (pinfunction "GND_8") (pintype "power_in"))
      (node (ref "U10") (pin "11") (pinfunction "V-_11") (pintype "power_in"))
      (node (ref "U11") (pin "13") (pinfunction "G_13") (pintype "input"))
      (node (ref "U11") (pin "8") (pinfunction "GND_8") (pintype "power_in"))
      (node (ref "U13") (pin "13") (pinfunction "G_13") (pintype "input"))
      (node (ref "U13") (pin "8") (pinfunction "GND_8") (pintype "power_in"))
      (node (ref "U2") (pin "6") (pinfunction "INH_6") (pintype "input"))
      (node (ref "U2") (pin "8") (pinfunction "GND_8") (pintype "power_in"))
      (node (ref "U3") (pin "3") (pinfunction "VSS_3") (pintype "power_in"))
      (node (ref "U4") (pin "3") (pinfunction "VSS_3") (pintype "power_in"))
      (node (ref "U5") (pin "3") (pinfunction "VSS_3") (pintype "power_in"))
      (node (ref "U6") (pin "3") (pinfunction "VSS_3") (pintype "power_in"))
      (node (ref "U7") (pin "2") (pinfunction "GND_2") (pintype "power_in"))
      (node (ref "U7B") (pin "2") (pinfunction "VSS_2") (pintype "power_in"))
      (node (ref "U8") (pin "4") (pinfunction "SD_4") (pintype "bidirectional"))
      (node (ref "U8") (pin "5") (pinfunction "GND1_5") (pintype "power_in"))
      (node (ref "U8") (pin "6") (pinfunction "GND2_6") (pintype "power_in"))
      (node (ref "U8") (pin "7") (pinfunction "GND3_7") (pintype "power_in"))
      (node (ref "U8") (pin "8") (pinfunction "GND4_8") (pintype "power_in"))
      (node (ref "U8B") (pin "2") (pinfunction "GNDSIG_2") (pintype "input"))
      (node (ref "U8B") (pin "3") (pinfunction "~{ON/OFF}_3") (pintype "input"))
      (node (ref "U8B") (pin "4") (pinfunction "GND_4") (pintype "power_in"))
      (node (ref "U9") (pin "11") (pinfunction "V-_11") (pintype "power_in"))
      (node (ref "X6") (pin "2") (pinfunction "2_2") (pintype "passive"))
    )
    (net (code "18") (name "I2CSCL") (class "Default")
      (node (ref "JP1") (pin "1") (pinfunction "1_1") (pintype "passive"))
      (node (ref "R62") (pin "2") (pinfunction "2_2") (pintype "passive"))
      (node (ref "U$1") (pin "PB6") (pinfunction "PB6_PB6") (pintype "bidirectional"))
    )
    (net (code "19") (name "I2CSDA") (class "Default")
      (node (ref "JP1") (pin "2") (pinfunction "2_2") (pintype "passive"))
      (node (ref "R63") (pin "2") (pinfunction "2_2") (pintype "passive"))
      (node (ref "U$1") (pin "PB7") (pinfunction "PB7_PB7") (pintype "bidirectional"))
    )
    (net (code "20") (name "ILAT") (class "Default")
      (node (ref "U$1") (pin "PA6") (pinfunction "PA6_PA6") (pintype "bidirectional"))
      (node (ref "U1") (pin "15") (pinfunction "SH/~{LD}_15") (pintype "input"))
      (node (ref "U2") (pin "15") (pinfunction "SH/~{LD}_15") (pintype "input"))
    )
    (net (code "21") (name "MISO") (class "Default")
      (node (ref "JP2") (pin "1") (pinfunction "1_1") (pintype "passive"))
      (node (ref "U$1") (pin "PB4") (pinfunction "PB4_PB4") (pintype "bidirectional"))
    )
    (net (code "22") (name "MISO2") (class "Default")
      (node (ref "SJ13") (pin "P$2") (pinfunction "2_P$2") (pintype "passive"))
      (node (ref "U$1") (pin "PC2") (pinfunction "PC2_PC2") (pintype "bidirectional"))
      (node (ref "U2") (pin "13") (pinfunction "QH_13") (pintype "output"))
    )
    (net (code "23") (name "MOSI") (class "Default")
      (node (ref "R20") (pin "1") (pinfunction "1_1") (pintype "passive"))
      (node (ref "SJ15") (pin "1") (pinfunction "1_1") (pintype "passive"))
      (node (ref "SJ17") (pin "P$2") (pinfunction "2_P$2") (pintype "passive"))
      (node (ref "U$1") (pin "PB5") (pinfunction "PB5_PB5") (pintype "bidirectional"))
      (node (ref "U11") (pin "14") (pinfunction "SER_14") (pintype "input"))
    )
    (net (code "24") (name "Net-(D2-PadA)") (class "Default")
      (node (ref "D2") (pin "A") (pinfunction "A_A") (pintype "passive"))
      (node (ref "JP4") (pin "4") (pinfunction "4_4") (pintype "passive"))
    )
    (net (code "25") (name "Net-(D2-PadC)") (class "Default")
      (node (ref "D2") (pin "C") (pinfunction "C_C") (pintype "passive"))
      (node (ref "JP4") (pin "1") (pinfunction "1_1") (pintype "passive"))
    )
    (net (code "26") (name "Net-(J1-Pad4)") (class "Default")
      (node (ref "J1") (pin "4") (pinfunction "4_4") (pintype "passive"))
      (node (ref "J2") (pin "4") (pinfunction "4_4") (pintype "passive"))
    )
    (net (code "27") (name "Net-(J1-Pad5)") (class "Default")
      (node (ref "J1") (pin "5") (pinfunction "5_5") (pintype "passive"))
      (node (ref "J2") (pin "5") (pinfunction "5_5") (pintype "passive"))
    )
    (net (code "28") (name "Net-(JP4-Pad3)") (class "Default")
      (node (ref "JP4") (pin "3") (pinfunction "3_3") (pintype "passive"))
      (node (ref "R40") (pin "2") (pinfunction "2_2") (pintype "passive"))
    )
    (net (code "29") (name "Net-(PORTA-Pad1)") (class "Default")
      (node (ref "PORTA") (pin "1") (pinfunction "1_1") (pintype "passive"))
      (node (ref "R44") (pin "2") (pinfunction "2_2") (pintype "passive"))
      (node (ref "R53") (pin "2") (pinfunction "2_2") (pintype "passive"))
      (node (ref "RN3") (pin "1") (pinfunction "1_1") (pintype "passive"))
      (node (ref "RN4") (pin "9") (pinfunction "9_9") (pintype "passive"))
      (node (ref "X1") (pin "1") (pinfunction "1_1") (pintype "passive"))
    )
    (net (code "30") (name "Net-(PORTB-Pad1)") (class "Default")
      (node (ref "PORTB") (pin "1") (pinfunction "1_1") (pintype "passive"))
      (node (ref "R35") (pin "2") (pinfunction "2_2") (pintype "passive"))
      (node (ref "R45") (pin "2") (pinfunction "2_2") (pintype "passive"))
      (node (ref "RN1") (pin "1") (pinfunction "1_1") (pintype "passive"))
      (node (ref "RN2") (pin "9") (pinfunction "9_9") (pintype "passive"))
      (node (ref "X2") (pin "1") (pinfunction "1_1") (pintype "passive"))
    )
    (net (code "31") (name "Net-(Q1-D)") (class "Default")
      (node (ref "Q1") (pin "3") (pinfunction "D_3") (pintype "passive"))
      (node (ref "U12") (pin "18") (pinfunction "O1_18") (pintype "open_collector"))
      (node (ref "X5") (pin "1") (pinfunction "1_1") (pintype "passive"))
    )
    (net (code "32") (name "Net-(Q1-G)") (class "Default")
      (node (ref "Q1") (pin "1") (pinfunction "G_1") (pintype "passive"))
      (node (ref "R3") (pin "2") (pinfunction "2_2") (pintype "passive"))
    )
    (net (code "33") (name "Net-(Q2-D)") (class "Default")
      (node (ref "Q2") (pin "3") (pinfunction "D_3") (pintype "passive"))
      (node (ref "U12") (pin "17") (pinfunction "O2_17") (pintype "open_collector"))
      (node (ref "X5") (pin "2") (pinfunction "2_2") (pintype "passive"))
    )
    (net (code "34") (name "Net-(Q2-G)") (class "Default")
      (node (ref "Q2") (pin "1") (pinfunction "G_1") (pintype "passive"))
      (node (ref "R4") (pin "2") (pinfunction "2_2") (pintype "passive"))
    )
    (net (code "35") (name "Net-(Q3-D)") (class "Default")
      (node (ref "Q3") (pin "3") (pinfunction "D_3") (pintype "passive"))
      (node (ref "U12") (pin "16") (pinfunction "O3_16") (pintype "open_collector"))
      (node (ref "X5") (pin "3") (pinfunction "3_3") (pintype "passive"))
    )
    (net (code "36") (name "Net-(Q3-G)") (class "Default")
      (node (ref "Q3") (pin "1") (pinfunction "G_1") (pintype "passive"))
      (node (ref "R5") (pin "2") (pinfunction "2_2") (pintype "passive"))
    )
    (net (code "37") (name "Net-(Q4-D)") (class "Default")
      (node (ref "Q4") (pin "3") (pinfunction "D_3") (pintype "passive"))
      (node (ref "U12") (pin "15") (pinfunction "O4_15") (pintype "open_collector"))
      (node (ref "X5") (pin "4") (pinfunction "4_4") (pintype "passive"))
    )
    (net (code "38") (name "Net-(Q4-G)") (class "Default")
      (node (ref "Q4") (pin "1") (pinfunction "G_1") (pintype "passive"))
      (node (ref "R6") (pin "2") (pinfunction "2_2") (pintype "passive"))
    )
    (net (code "39") (name "Net-(Q5-D)") (class "Default")
      (node (ref "Q5") (pin "3") (pinfunction "D_3") (pintype "passive"))
      (node (ref "U12") (pin "14") (pinfunction "O5_14") (pintype "open_collector"))
      (node (ref "X5") (pin "5") (pinfunction "5_5") (pintype "passive"))
    )
    (net (code "40") (name "Net-(Q5-G)") (class "Default")
      (node (ref "Q5") (pin "1") (pinfunction "G_1") (pintype "passive"))
      (node (ref "R7") (pin "2") (pinfunction "2_2") (pintype "passive"))
    )
    (net (code "41") (name "Net-(Q6-D)") (class "Default")
      (node (ref "Q6") (pin "3") (pinfunction "D_3") (pintype "passive"))
      (node (ref "U12") (pin "13") (pinfunction "O6_13") (pintype "open_collector"))
      (node (ref "X5") (pin "6") (pinfunction "6_6") (pintype "passive"))
    )
    (net (code "42") (name "Net-(Q6-G)") (class "Default")
      (node (ref "Q6") (pin "1") (pinfunction "G_1") (pintype "passive"))
      (node (ref "R8") (pin "2") (pinfunction "2_2") (pintype "passive"))
    )
    (net (code "43") (name "Net-(Q7-D)") (class "Default")
      (node (ref "Q7") (pin "3") (pinfunction "D_3") (pintype "passive"))
      (node (ref "U12") (pin "12") (pinfunction "O7_12") (pintype "open_collector"))
      (node (ref "X5") (pin "7") (pinfunction "7_7") (pintype "passive"))
    )
    (net (code "44") (name "Net-(Q7-G)") (class "Default")
      (node (ref "Q7") (pin "1") (pinfunction "G_1") (pintype "passive"))
      (node (ref "R9") (pin "2") (pinfunction "2_2") (pintype "passive"))
    )
    (net (code "45") (name "Net-(Q8-D)") (class "Default")
      (node (ref "Q8") (pin "3") (pinfunction "D_3") (pintype "passive"))
      (node (ref "U12") (pin "11") (pinfunction "O8_11") (pintype "open_collector"))
      (node (ref "X5") (pin "8") (pinfunction "8_8") (pintype "passive"))
    )
    (net (code "46") (name "Net-(Q8-G)") (class "Default")
      (node (ref "Q8") (pin "1") (pinfunction "G_1") (pintype "passive"))
      (node (ref "R10") (pin "2") (pinfunction "2_2") (pintype "passive"))
    )
    (net (code "47") (name "Net-(Q9-D)") (class "Default")
      (node (ref "Q9") (pin "3") (pinfunction "D_3") (pintype "passive"))
      (node (ref "U14") (pin "18") (pinfunction "O1_18") (pintype "open_collector"))
      (node (ref "X4") (pin "1") (pinfunction "1_1") (pintype "passive"))
    )
    (net (code "48") (name "Net-(Q9-G)") (class "Default")
      (node (ref "Q9") (pin "1") (pinfunction "G_1") (pintype "passive"))
      (node (ref "R11") (pin "2") (pinfunction "2_2") (pintype "passive"))
    )
    (net (code "49") (name "Net-(Q10-D)") (class "Default")
      (node (ref "Q10") (pin "3") (pinfunction "D_3") (pintype "passive"))
      (node (ref "U14") (pin "17") (pinfunction "O2_17") (pintype "open_collector"))
      (node (ref "X4") (pin "2") (pinfunction "2_2") (pintype "passive"))
    )
    (net (code "50") (name "Net-(Q10-G)") (class "Default")
      (node (ref "Q10") (pin "1") (pinfunction "G_1") (pintype "passive"))
      (node (ref "R12") (pin "2") (pinfunction "2_2") (pintype "passive"))
    )
    (net (code "51") (name "Net-(Q11-D)") (class "Default")
      (node (ref "Q11") (pin "3") (pinfunction "D_3") (pintype "passive"))
      (node (ref "U14") (pin "16") (pinfunction "O3_16") (pintype "open_collector"))
      (node (ref "X4") (pin "3") (pinfunction "3_3") (pintype "passive"))
    )
    (net (code "52") (name "Net-(Q11-G)") (class "Default")
      (node (ref "Q11") (pin "1") (pinfunction "G_1") (pintype "passive"))
      (node (ref "R13") (pin "2") (pinfunction "2_2") (pintype "passive"))
    )
    (net (code "53") (name "Net-(Q12-D)") (class "Default")
      (node (ref "Q12") (pin "3") (pinfunction "D_3") (pintype "passive"))
      (node (ref "U14") (pin "15") (pinfunction "O4_15") (pintype "open_collector"))
      (node (ref "X4") (pin "4") (pinfunction "4_4") (pintype "passive"))
    )
    (net (code "54") (name "Net-(Q12-G)") (class "Default")
      (node (ref "Q12") (pin "1") (pinfunction "G_1") (pintype "passive"))
      (node (ref "R14") (pin "2") (pinfunction "2_2") (pintype "passive"))
    )
    (net (code "55") (name "Net-(Q13-D)") (class "Default")
      (node (ref "Q13") (pin "3") (pinfunction "D_3") (pintype "passive"))
      (node (ref "U14") (pin "14") (pinfunction "O5_14") (pintype "open_collector"))
      (node (ref "X4") (pin "5") (pinfunction "5_5") (pintype "passive"))
    )
    (net (code "56") (name "Net-(Q13-G)") (class "Default")
      (node (ref "Q13") (pin "1") (pinfunction "G_1") (pintype "passive"))
      (node (ref "R15") (pin "2") (pinfunction "2_2") (pintype "passive"))
    )
    (net (code "57") (name "Net-(Q14-D)") (class "Default")
      (node (ref "Q14") (pin "3") (pinfunction "D_3") (pintype "passive"))
      (node (ref "U14") (pin "13") (pinfunction "O6_13") (pintype "open_collector"))
      (node (ref "X4") (pin "6") (pinfunction "6_6") (pintype "passive"))
    )
    (net (code "58") (name "Net-(Q14-G)") (class "Default")
      (node (ref "Q14") (pin "1") (pinfunction "G_1") (pintype "passive"))
      (node (ref "R16") (pin "2") (pinfunction "2_2") (pintype "passive"))
    )
    (net (code "59") (name "Net-(Q15-D)") (class "Default")
      (node (ref "Q15") (pin "3") (pinfunction "D_3") (pintype "passive"))
      (node (ref "U14") (pin "12") (pinfunction "O7_12") (pintype "open_collector"))
      (node (ref "X4") (pin "7") (pinfunction "7_7") (pintype "passive"))
    )
    (net (code "60") (name "Net-(Q15-G)") (class "Default")
      (node (ref "Q15") (pin "1") (pinfunction "G_1") (pintype "passive"))
      (node (ref "R17") (pin "2") (pinfunction "2_2") (pintype "passive"))
    )
    (net (code "61") (name "Net-(Q16-D)") (class "Default")
      (node (ref "Q16") (pin "3") (pinfunction "D_3") (pintype "passive"))
      (node (ref "U14") (pin "11") (pinfunction "O8_11") (pintype "open_collector"))
      (node (ref "X4") (pin "8") (pinfunction "8_8") (pintype "passive"))
    )
    (net (code "62") (name "Net-(Q16-G)") (class "Default")
      (node (ref "Q16") (pin "1") (pinfunction "G_1") (pintype "passive"))
      (node (ref "R18") (pin "2") (pinfunction "2_2") (pintype "passive"))
    )
    (net (code "63") (name "Net-(RN1A-2)") (class "Default")
      (node (ref "R35") (pin "1") (pinfunction "1_1") (pintype "passive"))
      (node (ref "RN1") (pin "16") (pinfunction "2_16") (pintype "passive"))
      (node (ref "U2") (pin "14") (pinfunction "H_14") (pintype "input"))
    )
    (net (code "64") (name "Net-(RN1B-1)") (class "Default")
      (node (ref "PORTB") (pin "2") (pinfunction "2_2") (pintype "passive"))
      (node (ref "R34") (pin "2") (pinfunction "2_2") (pintype "passive"))
      (node (ref "R46") (pin "2") (pinfunction "2_2") (pintype "passive"))
      (node (ref "RN1") (pin "2") (pinfunction "1_2") (pintype "passive"))
      (node (ref "RN2") (pin "8") (pinfunction "8_8") (pintype "passive"))
      (node (ref "X2") (pin "2") (pinfunction "2_2") (pintype "passive"))
    )
    (net (code "65") (name "Net-(RN1B-2)") (class "Default")
      (node (ref "R34") (pin "1") (pinfunction "1_1") (pintype "passive"))
      (node (ref "RN1") (pin "15") (pinfunction "2_15") (pintype "passive"))
      (node (ref "U2") (pin "12") (pinfunction "G_12") (pintype "input"))
    )
    (net (code "66") (name "Net-(RN1C-1)") (class "Default")
      (node (ref "PORTB") (pin "3") (pinfunction "3_3") (pintype "passive"))
      (node (ref "R33") (pin "2") (pinfunction "2_2") (pintype "passive"))
      (node (ref "R47") (pin "2") (pinfunction "2_2") (pintype "passive"))
      (node (ref "RN1") (pin "3") (pinfunction "1_3") (pintype "passive"))
      (node (ref "RN2") (pin "7") (pinfunction "7_7") (pintype "passive"))
      (node (ref "X2") (pin "3") (pinfunction "3_3") (pintype "passive"))
    )
    (net (code "67") (name "Net-(RN1C-2)") (class "Default")
      (node (ref "R33") (pin "1") (pinfunction "1_1") (pintype "passive"))
      (node (ref "RN1") (pin "14") (pinfunction "2_14") (pintype "passive"))
      (node (ref "U2") (pin "11") (pinfunction "F_11") (pintype "input"))
    )
    (net (code "68") (name "Net-(RN1D-1)") (class "Default")
      (node (ref "PORTB") (pin "4") (pinfunction "4_4") (pintype "passive"))
      (node (ref "R32") (pin "2") (pinfunction "2_2") (pintype "passive"))
      (node (ref "R48") (pin "2") (pinfunction "2_2") (pintype "passive"))
      (node (ref "RN1") (pin "4") (pinfunction "1_4") (pintype "passive"))
      (node (ref "RN2") (pin "6") (pinfunction "6_6") (pintype "passive"))
      (node (ref "X2") (pin "4") (pinfunction "4_4") (pintype "passive"))
    )
    (net (code "69") (name "Net-(RN1D-2)") (class "Default")
      (node (ref "R32") (pin "1") (pinfunction "1_1") (pintype "passive"))
      (node (ref "RN1") (pin "13") (pinfunction "2_13") (pintype "passive"))
      (node (ref "U2") (pin "10") (pinfunction "E_10") (pintype "input"))
    )
    (net (code "70") (name "Net-(RN1E-1)") (class "Default")
      (node (ref "PORTB") (pin "7") (pinfunction "7_7") (pintype "passive"))
      (node (ref "R31") (pin "2") (pinfunction "2_2") (pintype "passive"))
      (node (ref "R49") (pin "2") (pinfunction "2_2") (pintype "passive"))
      (node (ref "RN1") (pin "5") (pinfunction "1_5") (pintype "passive"))
      (node (ref "RN2") (pin "5") (pinfunction "5_5") (pintype "passive"))
      (node (ref "X2") (pin "5") (pinfunction "5_5") (pintype "passive"))
    )
    (net (code "71") (name "Net-(RN1E-2)") (class "Default")
      (node (ref "R31") (pin "1") (pinfunction "1_1") (pintype "passive"))
      (node (ref "RN1") (pin "12") (pinfunction "2_12") (pintype "passive"))
      (node (ref "U2") (pin "5") (pinfunction "D_5") (pintype "input"))
    )
    (net (code "72") (name "Net-(RN1F-1)") (class "Default")
      (node (ref "PORTB") (pin "8") (pinfunction "8_8") (pintype "passive"))
      (node (ref "R30") (pin "2") (pinfunction "2_2") (pintype "passive"))
      (node (ref "R50") (pin "2") (pinfunction "2_2") (pintype "passive"))
      (node (ref "RN1") (pin "6") (pinfunction "1_6") (pintype "passive"))
      (node (ref "RN2") (pin "4") (pinfunction "4_4") (pintype "passive"))
      (node (ref "X2") (pin "6") (pinfunction "6_6") (pintype "passive"))
    )
    (net (code "73") (name "Net-(RN1F-2)") (class "Default")
      (node (ref "R30") (pin "1") (pinfunction "1_1") (pintype "passive"))
      (node (ref "RN1") (pin "11") (pinfunction "2_11") (pintype "passive"))
      (node (ref "U2") (pin "4") (pinfunction "C_4") (pintype "input"))
    )
    (net (code "74") (name "Net-(RN1G-1)") (class "Default")
      (node (ref "PORTB") (pin "9") (pinfunction "9_9") (pintype "passive"))
      (node (ref "R29") (pin "2") (pinfunction "2_2") (pintype "passive"))
      (node (ref "R51") (pin "2") (pinfunction "2_2") (pintype "passive"))
      (node (ref "RN1") (pin "7") (pinfunction "1_7") (pintype "passive"))
      (node (ref "RN2") (pin "3") (pinfunction "3_3") (pintype "passive"))
      (node (ref "X2") (pin "7") (pinfunction "7_7") (pintype "passive"))
    )
    (net (code "75") (name "Net-(RN1G-2)") (class "Default")
      (node (ref "R29") (pin "1") (pinfunction "1_1") (pintype "passive"))
      (node (ref "RN1") (pin "10") (pinfunction "2_10") (pintype "passive"))
      (node (ref "U2") (pin "3") (pinfunction "B_3") (pintype "input"))
    )
    (net (code "76") (name "Net-(RN1H-1)") (class "Default")
      (node (ref "PORTB") (pin "10") (pinfunction "10_10") (pintype "passive"))
      (node (ref "R28") (pin "2") (pinfunction "2_2") (pintype "passive"))
      (node (ref "R52") (pin "2") (pinfunction "2_2") (pintype "passive"))
      (node (ref "RN1") (pin "8") (pinfunction "1_8") (pintype "passive"))
      (node (ref "RN2") (pin "2") (pinfunction "2_2") (pintype "passive"))
      (node (ref "X2") (pin "8") (pinfunction "8_8") (pintype "passive"))
    )
    (net (code "77") (name "Net-(RN1H-2)") (class "Default")
      (node (ref "R28") (pin "1") (pinfunction "1_1") (pintype "passive"))
      (node (ref "RN1") (pin "9") (pinfunction "2_9") (pintype "passive"))
      (node (ref "U2") (pin "2") (pinfunction "A_2") (pintype "input"))
    )
    (net (code "78") (name "Net-(RN3A-2)") (class "Default")
      (node (ref "R44") (pin "1") (pinfunction "1_1") (pintype "passive"))
      (node (ref "RN3") (pin "16") (pinfunction "2_16") (pintype "passive"))
      (node (ref "U1") (pin "14") (pinfunction "H_14") (pintype "input"))
    )
    (net (code "79") (name "Net-(RN3B-1)") (class "Default")
      (node (ref "PORTA") (pin "2") (pinfunction "2_2") (pintype "passive"))
      (node (ref "R43") (pin "2") (pinfunction "2_2") (pintype "passive"))
      (node (ref "R54") (pin "2") (pinfunction "2_2") (pintype "passive"))
      (node (ref "RN3") (pin "2") (pinfunction "1_2") (pintype "passive"))
      (node (ref "RN4") (pin "8") (pinfunction "8_8") (pintype "passive"))
      (node (ref "X1") (pin "2") (pinfunction "2_2") (pintype "passive"))
    )
    (net (code "80") (name "Net-(RN3B-2)") (class "Default")
      (node (ref "R43") (pin "1") (pinfunction "1_1") (pintype "passive"))
      (node (ref "RN3") (pin "15") (pinfunction "2_15") (pintype "passive"))
      (node (ref "U1") (pin "12") (pinfunction "G_12") (pintype "input"))
    )
    (net (code "81") (name "Net-(RN3C-1)") (class "Default")
      (node (ref "PORTA") (pin "3") (pinfunction "3_3") (pintype "passive"))
      (node (ref "R42") (pin "2") (pinfunction "2_2") (pintype "passive"))
      (node (ref "R55") (pin "2") (pinfunction "2_2") (pintype "passive"))
      (node (ref "RN3") (pin "3") (pinfunction "1_3") (pintype "passive"))
      (node (ref "RN4") (pin "7") (pinfunction "7_7") (pintype "passive"))
      (node (ref "X1") (pin "3") (pinfunction "3_3") (pintype "passive"))
    )
    (net (code "82") (name "Net-(RN3C-2)") (class "Default")
      (node (ref "R42") (pin "1") (pinfunction "1_1") (pintype "passive"))
      (node (ref "RN3") (pin "14") (pinfunction "2_14") (pintype "passive"))
      (node (ref "U1") (pin "11") (pinfunction "F_11") (pintype "input"))
    )
    (net (code "83") (name "Net-(RN3D-1)") (class "Default")
      (node (ref "PORTA") (pin "4") (pinfunction "4_4") (pintype "passive"))
      (node (ref "R41") (pin "2") (pinfunction "2_2") (pintype "passive"))
      (node (ref "R56") (pin "2") (pinfunction "2_2") (pintype "passive"))
      (node (ref "RN3") (pin "4") (pinfunction "1_4") (pintype "passive"))
      (node (ref "RN4") (pin "6") (pinfunction "6_6") (pintype "passive"))
      (node (ref "X1") (pin "4") (pinfunction "4_4") (pintype "passive"))
    )
    (net (code "84") (name "Net-(RN3D-2)") (class "Default")
      (node (ref "R41") (pin "1") (pinfunction "1_1") (pintype "passive"))
      (node (ref "RN3") (pin "13") (pinfunction "2_13") (pintype "passive"))
      (node (ref "U1") (pin "10") (pinfunction "E_10") (pintype "input"))
    )
    (net (code "85") (name "Net-(RN3E-1)") (class "Default")
      (node (ref "PORTA") (pin "7") (pinfunction "7_7") (pintype "passive"))
      (node (ref "R39") (pin "2") (pinfunction "2_2") (pintype "passive"))
      (node (ref "R57") (pin "2") (pinfunction "2_2") (pintype "passive"))
      (node (ref "RN3") (pin "5") (pinfunction "1_5") (pintype "passive"))
      (node (ref "RN4") (pin "5") (pinfunction "5_5") (pintype "passive"))
      (node (ref "X1") (pin "5") (pinfunction "5_5") (pintype "passive"))
    )
    (net (code "86") (name "Net-(RN3E-2)") (class "Default")
      (node (ref "R39") (pin "1") (pinfunction "1_1") (pintype "passive"))
      (node (ref "RN3") (pin "12") (pinfunction "2_12") (pintype "passive"))
      (node (ref "U1") (pin "5") (pinfunction "D_5") (pintype "input"))
    )
    (net (code "87") (name "Net-(RN3F-1)") (class "Default")
      (node (ref "PORTA") (pin "8") (pinfunction "8_8") (pintype "passive"))
      (node (ref "R38") (pin "2") (pinfunction "2_2") (pintype "passive"))
      (node (ref "R58") (pin "2") (pinfunction "2_2") (pintype "passive"))
      (node (ref "RN3") (pin "6") (pinfunction "1_6") (pintype "passive"))
      (node (ref "RN4") (pin "4") (pinfunction "4_4") (pintype "passive"))
      (node (ref "X1") (pin "6") (pinfunction "6_6") (pintype "passive"))
    )
    (net (code "88") (name "Net-(RN3F-2)") (class "Default")
      (node (ref "R38") (pin "1") (pinfunction "1_1") (pintype "passive"))
      (node (ref "RN3") (pin "11") (pinfunction "2_11") (pintype "passive"))
      (node (ref "U1") (pin "4") (pinfunction "C_4") (pintype "input"))
    )
    (net (code "89") (name "Net-(RN3G-1)") (class "Default")
      (node (ref "PORTA") (pin "9") (pinfunction "9_9") (pintype "passive"))
      (node (ref "R37") (pin "2") (pinfunction "2_2") (pintype "passive"))
      (node (ref "R59") (pin "2") (pinfunction "2_2") (pintype "passive"))
      (node (ref "RN3") (pin "7") (pinfunction "1_7") (pintype "passive"))
      (node (ref "RN4") (pin "3") (pinfunction "3_3") (pintype "passive"))
      (node (ref "X1") (pin "7") (pinfunction "7_7") (pintype "passive"))
    )
    (net (code "90") (name "Net-(RN3G-2)") (class "Default")
      (node (ref "R37") (pin "1") (pinfunction "1_1") (pintype "passive"))
      (node (ref "RN3") (pin "10") (pinfunction "2_10") (pintype "passive"))
      (node (ref "U1") (pin "3") (pinfunction "B_3") (pintype "input"))
    )
    (net (code "91") (name "Net-(RN3H-1)") (class "Default")
      (node (ref "PORTA") (pin "10") (pinfunction "10_10") (pintype "passive"))
      (node (ref "R36") (pin "2") (pinfunction "2_2") (pintype "passive"))
      (node (ref "R60") (pin "2") (pinfunction "2_2") (pintype "passive"))
      (node (ref "RN3") (pin "8") (pinfunction "1_8") (pintype "passive"))
      (node (ref "RN4") (pin "2") (pinfunction "2_2") (pintype "passive"))
      (node (ref "X1") (pin "8") (pinfunction "8_8") (pintype "passive"))
    )
    (net (code "92") (name "Net-(RN3H-2)") (class "Default")
      (node (ref "R36") (pin "1") (pinfunction "1_1") (pintype "passive"))
      (node (ref "RN3") (pin "9") (pinfunction "2_9") (pintype "passive"))
      (node (ref "U1") (pin "2") (pinfunction "A_2") (pintype "input"))
    )
    (net (code "93") (name "Net-(SJ1-1)") (class "Default")
      (node (ref "SJ1") (pin "P$1") (pinfunction "1_P$1") (pintype "passive"))
      (node (ref "SJ2") (pin "P$1") (pinfunction "1_P$1") (pintype "passive"))
      (node (ref "SJ3") (pin "1") (pinfunction "1_1") (pintype "passive"))
      (node (ref "U12") (pin "9") (pinfunction "GND_9") (pintype "power_in"))
    )
    (net (code "94") (name "Net-(SJ4-1)") (class "Default")
      (node (ref "SJ4") (pin "P$1") (pinfunction "1_P$1") (pintype "passive"))
      (node (ref "SJ5") (pin "P$1") (pinfunction "1_P$1") (pintype "passive"))
      (node (ref "SJ6") (pin "P$1") (pinfunction "1_P$1") (pintype "passive"))
      (node (ref "U12") (pin "10") (pinfunction "CD+_10") (pintype "passive"))
    )
    (net (code "95") (name "Net-(SJ7-1)") (class "Default")
      (node (ref "SJ7") (pin "P$1") (pinfunction "1_P$1") (pintype "passive"))
      (node (ref "SJ8") (pin "P$1") (pinfunction "1_P$1") (pintype "passive"))
      (node (ref "SJ9") (pin "1") (pinfunction "1_1") (pintype "passive"))
      (node (ref "U14") (pin "9") (pinfunction "GND_9") (pintype "power_in"))
    )
    (net (code "96") (name "Net-(SJ10-1)") (class "Default")
      (node (ref "SJ10") (pin "P$1") (pinfunction "1_P$1") (pintype "passive"))
      (node (ref "SJ11") (pin "P$1") (pinfunction "1_P$1") (pintype "passive"))
      (node (ref "SJ12") (pin "P$1") (pinfunction "1_P$1") (pintype "passive"))
      (node (ref "U14") (pin "10") (pinfunction "CD+_10") (pintype "passive"))
    )
    (net (code "97") (name "Net-(SJ13-1)") (class "Default")
      (node (ref "SJ13") (pin "P$1") (pinfunction "1_P$1") (pintype "passive"))
      (node (ref "U$1") (pin "PB14") (pinfunction "PB14_PB14") (pintype "bidirectional"))
    )
    (net (code "98") (name "Net-(SJ14-1)") (class "Default")
      (node (ref "SJ14") (pin "P$1") (pinfunction "1_P$1") (pintype "passive"))
      (node (ref "U$1") (pin "VIN2") (pinfunction "VIN2_VIN2") (pintype "power_in"))
    )
    (net (code "99") (name "Net-(SJ16-2)") (class "Default")
      (node (ref "JP2") (pin "2") (pinfunction "2_2") (pintype "passive"))
      (node (ref "SJ15") (pin "2") (pinfunction "2_2") (pintype "passive"))
      (node (ref "SJ16") (pin "P$2") (pinfunction "2_P$2") (pintype "passive"))
    )
    (net (code "100") (name "Net-(SJ18-2)") (class "Default")
      (node (ref "SJ18") (pin "P$2") (pinfunction "2_P$2") (pintype "passive"))
      (node (ref "U7") (pin "5") (pinfunction "VREF_5") (pintype "output"))
      (node (ref "U7B") (pin "5") (pinfunction "VREF_5") (pintype "bidirectional"))
    )
    (net (code "101") (name "Net-(U3A-O)") (class "Default")
      (node (ref "PORTC") (pin "1") (pinfunction "1_1") (pintype "passive"))
      (node (ref "U3") (pin "7") (pinfunction "O_7") (pintype "output"))
      (node (ref "U9") (pin "7") (pinfunction "OUT_7") (pintype "output"))
      (node (ref "X3") (pin "1") (pinfunction "1_1") (pintype "passive"))
    )
    (net (code "102") (name "Net-(U3B-O)") (class "Default")
      (node (ref "PORTC") (pin "2") (pinfunction "2_2") (pintype "passive"))
      (node (ref "U3") (pin "5") (pinfunction "O_5") (pintype "output"))
      (node (ref "U9") (pin "8") (pinfunction "OUT_8") (pintype "output"))
      (node (ref "X3") (pin "2") (pinfunction "2_2") (pintype "passive"))
    )
    (net (code "103") (name "Net-(U4A-O)") (class "Default")
      (node (ref "PORTC") (pin "4") (pinfunction "4_4") (pintype "passive"))
      (node (ref "U4") (pin "7") (pinfunction "O_7") (pintype "output"))
      (node (ref "U9") (pin "14") (pinfunction "OUT_14") (pintype "output"))
      (node (ref "X3") (pin "4") (pinfunction "4_4") (pintype "passive"))
    )
    (net (code "104") (name "Net-(U4B-O)") (class "Default")
      (node (ref "PORTC") (pin "3") (pinfunction "3_3") (pintype "passive"))
      (node (ref "U4") (pin "5") (pinfunction "O_5") (pintype "output"))
      (node (ref "U9") (pin "1") (pinfunction "OUT_1") (pintype "output"))
      (node (ref "X3") (pin "3") (pinfunction "3_3") (pintype "passive"))
    )
    (net (code "105") (name "Net-(U7-RS)") (class "Default")
      (node (ref "R61") (pin "1") (pinfunction "1_1") (pintype "passive"))
      (node (ref "U7") (pin "8") (pinfunction "RS_8") (pintype "input"))
      (node (ref "U7B") (pin "8") (pinfunction "RS_8") (pintype "bidirectional"))
    )
    (net (code "106") (name "Net-(U8-VOUT)") (class "Default")
      (node (ref "D1") (pin "C") (pinfunction "C_C") (pintype "passive"))
      (node (ref "L1") (pin "2") (pinfunction "2_2") (pintype "passive"))
      (node (ref "U8") (pin "2") (pinfunction "VOUT_2") (pintype "bidirectional"))
      (node (ref "U8B") (pin "7") (pinfunction "OUT_7") (pintype "passive"))
    )
    (net (code "107") (name "Net-(U10A--IN)") (class "Default")
      (node (ref "R1") (pin "1") (pinfunction "1_1") (pintype "passive"))
      (node (ref "R2") (pin "2") (pinfunction "2_2") (pintype "passive"))
      (node (ref "U10") (pin "13") (pinfunction "-IN_13") (pintype "input"))
      (node (ref "U10") (pin "2") (pinfunction "-IN_2") (pintype "input"))
      (node (ref "U10") (pin "6") (pinfunction "-IN_6") (pintype "input"))
      (node (ref "U10") (pin "9") (pinfunction "-IN_9") (pintype "input"))
      (node (ref "U9") (pin "13") (pinfunction "-IN_13") (pintype "input"))
      (node (ref "U9") (pin "2") (pinfunction "-IN_2") (pintype "input"))
      (node (ref "U9") (pin "6") (pinfunction "-IN_6") (pintype "input"))
      (node (ref "U9") (pin "9") (pinfunction "-IN_9") (pintype "input"))
    )
    (net (code "108") (name "Net-(U10A-OUT)") (class "Default")
      (node (ref "PORTC") (pin "9") (pinfunction "9_9") (pintype "passive"))
      (node (ref "U10") (pin "1") (pinfunction "OUT_1") (pintype "output"))
      (node (ref "U6") (pin "5") (pinfunction "O_5") (pintype "output"))
      (node (ref "X3") (pin "7") (pinfunction "7_7") (pintype "passive"))
    )
    (net (code "109") (name "Net-(U10B-OUT)") (class "Default")
      (node (ref "PORTC") (pin "7") (pinfunction "7_7") (pintype "passive"))
      (node (ref "U10") (pin "7") (pinfunction "OUT_7") (pintype "output"))
      (node (ref "U5") (pin "7") (pinfunction "O_7") (pintype "output"))
      (node (ref "X3") (pin "5") (pinfunction "5_5") (pintype "passive"))
    )
    (net (code "110") (name "Net-(U10C-OUT)") (class "Default")
      (node (ref "PORTC") (pin "8") (pinfunction "8_8") (pintype "passive"))
      (node (ref "U10") (pin "8") (pinfunction "OUT_8") (pintype "output"))
      (node (ref "U5") (pin "5") (pinfunction "O_5") (pintype "output"))
      (node (ref "X3") (pin "6") (pinfunction "6_6") (pintype "passive"))
    )
    (net (code "111") (name "Net-(U10D-OUT)") (class "Default")
      (node (ref "PORTC") (pin "10") (pinfunction "10_10") (pintype "passive"))
      (node (ref "U10") (pin "14") (pinfunction "OUT_14") (pintype "output"))
      (node (ref "U6") (pin "7") (pinfunction "O_7") (pintype "output"))
      (node (ref "X3") (pin "8") (pinfunction "8_8") (pintype "passive"))
    )
    (net (code "112") (name "Net-(U11A-QA)") (class "Default")
      (node (ref "R3") (pin "1") (pinfunction "1_1") (pintype "passive"))
      (node (ref "U11") (pin "15") (pinfunction "QA_15") (pintype "tri_state"))
      (node (ref "U12") (pin "1") (pinfunction "I1_1") (pintype "input"))
    )
    (net (code "113") (name "Net-(U11A-QB)") (class "Default")
      (node (ref "R4") (pin "1") (pinfunction "1_1") (pintype "passive"))
      (node (ref "U11") (pin "1") (pinfunction "QB_1") (pintype "tri_state"))
      (node (ref "U12") (pin "2") (pinfunction "I2_2") (pintype "input"))
    )
    (net (code "114") (name "Net-(U11A-QC)") (class "Default")
      (node (ref "R5") (pin "1") (pinfunction "1_1") (pintype "passive"))
      (node (ref "U11") (pin "2") (pinfunction "QC_2") (pintype "tri_state"))
      (node (ref "U12") (pin "3") (pinfunction "I3_3") (pintype "input"))
    )
    (net (code "115") (name "Net-(U11A-QD)") (class "Default")
      (node (ref "R6") (pin "1") (pinfunction "1_1") (pintype "passive"))
      (node (ref "U11") (pin "3") (pinfunction "QD_3") (pintype "tri_state"))
      (node (ref "U12") (pin "4") (pinfunction "I4_4") (pintype "input"))
    )
    (net (code "116") (name "Net-(U11A-QE)") (class "Default")
      (node (ref "R7") (pin "1") (pinfunction "1_1") (pintype "passive"))
      (node (ref "U11") (pin "4") (pinfunction "QE_4") (pintype "tri_state"))
      (node (ref "U12") (pin "5") (pinfunction "I5_5") (pintype "input"))
    )
    (net (code "117") (name "Net-(U11A-QF)") (class "Default")
      (node (ref "R8") (pin "1") (pinfunction "1_1") (pintype "passive"))
      (node (ref "U11") (pin "5") (pinfunction "QF_5") (pintype "tri_state"))
      (node (ref "U12") (pin "6") (pinfunction "I6_6") (pintype "input"))
    )
    (net (code "118") (name "Net-(U11A-QG)") (class "Default")
      (node (ref "R9") (pin "1") (pinfunction "1_1") (pintype "passive"))
      (node (ref "U11") (pin "6") (pinfunction "QG_6") (pintype "tri_state"))
      (node (ref "U12") (pin "7") (pinfunction "I7_7") (pintype "input"))
    )
    (net (code "119") (name "Net-(U11A-QH)") (class "Default")
      (node (ref "R10") (pin "1") (pinfunction "1_1") (pintype "passive"))
      (node (ref "U11") (pin "7") (pinfunction "QH_7") (pintype "tri_state"))
      (node (ref "U12") (pin "8") (pinfunction "I8_8") (pintype "input"))
    )
    (net (code "120") (name "Net-(U13A-QA)") (class "Default")
      (node (ref "R11") (pin "1") (pinfunction "1_1") (pintype "passive"))
      (node (ref "U13") (pin "15") (pinfunction "QA_15") (pintype "tri_state"))
      (node (ref "U14") (pin "1") (pinfunction "I1_1") (pintype "input"))
    )
    (net (code "121") (name "Net-(U13A-QB)") (class "Default")
      (node (ref "R12") (pin "1") (pinfunction "1_1") (pintype "passive"))
      (node (ref "U13") (pin "1") (pinfunction "QB_1") (pintype "tri_state"))
      (node (ref "U14") (pin "2") (pinfunction "I2_2") (pintype "input"))
    )
    (net (code "122") (name "Net-(U13A-QC)") (class "Default")
      (node (ref "R13") (pin "1") (pinfunction "1_1") (pintype "passive"))
      (node (ref "U13") (pin "2") (pinfunction "QC_2") (pintype "tri_state"))
      (node (ref "U14") (pin "3") (pinfunction "I3_3") (pintype "input"))
    )
    (net (code "123") (name "Net-(U13A-QD)") (class "Default")
      (node (ref "R14") (pin "1") (pinfunction "1_1") (pintype "passive"))
      (node (ref "U13") (pin "3") (pinfunction "QD_3") (pintype "tri_state"))
      (node (ref "U14") (pin "4") (pinfunction "I4_4") (pintype "input"))
    )
    (net (code "124") (name "Net-(U13A-QE)") (class "Default")
      (node (ref "R15") (pin "1") (pinfunction "1_1") (pintype "passive"))
      (node (ref "U13") (pin "4") (pinfunction "QE_4") (pintype "tri_state"))
      (node (ref "U14") (pin "5") (pinfunction "I5_5") (pintype "input"))
    )
    (net (code "125") (name "Net-(U13A-QF)") (class "Default")
      (node (ref "R16") (pin "1") (pinfunction "1_1") (pintype "passive"))
      (node (ref "U13") (pin "5") (pinfunction "QF_5") (pintype "tri_state"))
      (node (ref "U14") (pin "6") (pinfunction "I6_6") (pintype "input"))
    )
    (net (code "126") (name "Net-(U13A-QG)") (class "Default")
      (node (ref "R17") (pin "1") (pinfunction "1_1") (pintype "passive"))
      (node (ref "U13") (pin "6") (pinfunction "QG_6") (pintype "tri_state"))
      (node (ref "U14") (pin "7") (pinfunction "I7_7") (pintype "input"))
    )
    (net (code "127") (name "Net-(U13A-QH)") (class "Default")
      (node (ref "R18") (pin "1") (pinfunction "1_1") (pintype "passive"))
      (node (ref "U13") (pin "7") (pinfunction "QH_7") (pintype "tri_state"))
      (node (ref "U14") (pin "8") (pinfunction "I8_8") (pintype "input"))
    )
    (net (code "128") (name "OLAT") (class "Default")
      (node (ref "R21") (pin "1") (pinfunction "1_1") (pintype "passive"))
      (node (ref "U$1") (pin "PA8") (pinfunction "PA8_PA8") (pintype "bidirectional"))
      (node (ref "U11") (pin "12") (pinfunction "RCK_12") (pintype "input"))
      (node (ref "U13") (pin "12") (pinfunction "RCK_12") (pintype "input"))
    )
    (net (code "129") (name "SCK") (class "Default")
      (node (ref "JP2") (pin "3") (pinfunction "3_3") (pintype "passive"))
      (node (ref "R19") (pin "1") (pinfunction "1_1") (pintype "passive"))
      (node (ref "U$1") (pin "PB3") (pinfunction "PB3_PB3") (pintype "bidirectional"))
      (node (ref "U11") (pin "11") (pinfunction "SCK_11") (pintype "input"))
      (node (ref "U13") (pin "11") (pinfunction "SCK_11") (pintype "input"))
    )
    (net (code "130") (name "SCK2") (class "Default")
      (node (ref "U$1") (pin "PB10") (pinfunction "PB10_PB10") (pintype "bidirectional"))
      (node (ref "U1") (pin "7") (pinfunction "CLK_7") (pintype "input"))
      (node (ref "U2") (pin "7") (pinfunction "CLK_7") (pintype "input"))
    )
    (net (code "131") (name "SLNK1") (class "Default")
      (node (ref "SJ17") (pin "P$1") (pinfunction "1_P$1") (pintype "passive"))
      (node (ref "U11") (pin "9") (pinfunction "QH*_9") (pintype "tri_state"))
      (node (ref "U13") (pin "14") (pinfunction "SER_14") (pintype "input"))
    )
    (net (code "132") (name "SLNK2") (class "Default")
      (node (ref "SJ16") (pin "P$1") (pinfunction "1_P$1") (pintype "passive"))
      (node (ref "U13") (pin "9") (pinfunction "QH*_9") (pintype "tri_state"))
    )
    (net (code "133") (name "SLNK3") (class "Default")
      (node (ref "U1") (pin "13") (pinfunction "QH_13") (pintype "output"))
      (node (ref "U2") (pin "1") (pinfunction "SER_1") (pintype "input"))
    )
    (net (code "134") (name "SRV1") (class "Default")
      (node (ref "JP5") (pin "2") (pinfunction "2_2") (pintype "passive"))
      (node (ref "R24") (pin "2") (pinfunction "2_2") (pintype "passive"))
      (node (ref "U$1") (pin "PC9") (pinfunction "PC9_PC9") (pintype "bidirectional"))
    )
    (net (code "135") (name "SRV2") (class "Default")
      (node (ref "JP5") (pin "1") (pinfunction "1_1") (pintype "passive"))
      (node (ref "R25") (pin "2") (pinfunction "2_2") (pintype "passive"))
      (node (ref "U$1") (pin "PC7") (pinfunction "PC7_PC7") (pintype "bidirectional"))
    )
    (net (code "136") (name "SRV3") (class "Default")
      (node (ref "JP6") (pin "2") (pinfunction "2_2") (pintype "passive"))
      (node (ref "R26") (pin "2") (pinfunction "2_2") (pintype "passive"))
      (node (ref "U$1") (pin "PC8") (pinfunction "PC8_PC8") (pintype "bidirectional"))
    )
    (net (code "137") (name "SRV4") (class "Default")
      (node (ref "JP6") (pin "1") (pinfunction "1_1") (pintype "passive"))
      (node (ref "R27") (pin "2") (pinfunction "2_2") (pintype "passive"))
      (node (ref "U$1") (pin "PC6") (pinfunction "PC6_PC6") (pintype "bidirectional"))
    )
    (net (code "138") (name "SRV5") (class "Default")
      (node (ref "JP7") (pin "2") (pinfunction "2_2") (pintype "passive"))
      (node (ref "R64") (pin "2") (pinfunction "2_2") (pintype "passive"))
      (node (ref "U$1") (pin "PF1-PH1") (pinfunction "PF1-PH1_PF1-PH1") (pintype "bidirectional"))
    )
    (net (code "139") (name "SRV6") (class "Default")
      (node (ref "JP7") (pin "1") (pinfunction "1_1") (pintype "passive"))
      (node (ref "R65") (pin "2") (pinfunction "2_2") (pintype "passive"))
      (node (ref "U$1") (pin "PA15") (pinfunction "PA15_PA15") (pintype "bidirectional"))
    )
    (net (code "140") (name "SRV7") (class "Default")
      (node (ref "JP8") (pin "2") (pinfunction "2_2") (pintype "passive"))
      (node (ref "R66") (pin "2") (pinfunction "2_2") (pintype "passive"))
      (node (ref "U$1") (pin "PC12") (pinfunction "PC12_PC12") (pintype "bidirectional"))
    )
    (net (code "141") (name "SRV8") (class "Default")
      (node (ref "JP8") (pin "1") (pinfunction "1_1") (pintype "passive"))
      (node (ref "R67") (pin "2") (pinfunction "2_2") (pintype "passive"))
      (node (ref "U$1") (pin "PD2") (pinfunction "PD2_PD2") (pintype "bidirectional"))
    )
    (net (code "142") (name "TDRV1") (class "Default")
      (node (ref "U$1") (pin "PB12") (pinfunction "PB12_PB12") (pintype "bidirectional"))
      (node (ref "U10") (pin "12") (pinfunction "+IN_12") (pintype "input"))
      (node (ref "U6") (pin "2") (pinfunction "I_2") (pintype "input"))
    )
    (net (code "143") (name "TDRV2") (class "Default")
      (node (ref "U$1") (pin "PB2") (pinfunction "PB2_PB2") (pintype "bidirectional"))
      (node (ref "U10") (pin "3") (pinfunction "+IN_3") (pintype "input"))
      (node (ref "U6") (pin "4") (pinfunction "I_4") (pintype "input"))
    )
    (net (code "144") (name "TDRV3") (class "Default")
      (node (ref "U$1") (pin "PB15") (pinfunction "PB15_PB15") (pintype "bidirectional"))
      (node (ref "U10") (pin "10") (pinfunction "+IN_10") (pintype "input"))
      (node (ref "U5") (pin "4") (pinfunction "I_4") (pintype "input"))
    )
    (net (code "145") (name "TDRV4") (class "Default")
      (node (ref "U$1") (pin "PB1") (pinfunction "PB1_PB1") (pintype "bidirectional"))
      (node (ref "U10") (pin "5") (pinfunction "+IN_5") (pintype "input"))
      (node (ref "U5") (pin "2") (pinfunction "I_2") (pintype "input"))
    )
    (net (code "146") (name "TDRV5") (class "Default")
      (node (ref "U$1") (pin "PA0") (pinfunction "PA0_PA0") (pintype "bidirectional"))
      (node (ref "U4") (pin "2") (pinfunction "I_2") (pintype "input"))
      (node (ref "U9") (pin "12") (pinfunction "+IN_12") (pintype "input"))
    )
    (net (code "147") (name "TDRV6") (class "Default")
      (node (ref "U$1") (pin "PA4") (pinfunction "PA4_PA4") (pintype "bidirectional"))
      (node (ref "U4") (pin "4") (pinfunction "I_4") (pintype "input"))
      (node (ref "U9") (pin "3") (pinfunction "+IN_3") (pintype "input"))
    )
    (net (code "148") (name "TDRV7") (class "Default")
      (node (ref "U$1") (pin "PC3") (pinfunction "PC3_PC3") (pintype "bidirectional"))
      (node (ref "U3") (pin "4") (pinfunction "I_4") (pintype "input"))
      (node (ref "U9") (pin "10") (pinfunction "+IN_10") (pintype "input"))
    )
    (net (code "149") (name "TDRV8") (class "Default")
      (node (ref "U$1") (pin "PC0") (pinfunction "PC0_PC0") (pintype "bidirectional"))
      (node (ref "U3") (pin "2") (pinfunction "I_2") (pintype "input"))
      (node (ref "U9") (pin "5") (pinfunction "+IN_5") (pintype "input"))
    )
    (net (code "150") (name "V+") (class "Default")
      (node (ref "C1") (pin "1") (pinfunction "1_1") (pintype "passive"))
      (node (ref "C2") (pin "+") (pinfunction "+_+") (pintype "passive"))
      (node (ref "L1") (pin "1") (pinfunction "1_1") (pintype "passive"))
      (node (ref "U$1") (pin "E5V") (pinfunction "E5V_E5V") (pintype "power_in"))
      (node (ref "U8") (pin "3") (pinfunction "FB_3") (pintype "bidirectional"))
      (node (ref "U8B") (pin "1") (pinfunction "FB_1") (pintype "input"))
    )
    (net (code "151") (name "unconnected-(H1-MOUNT-PadB3,3)") (class "Default")
      (node (ref "H1") (pin "B3,3") (pinfunction "MOUNT_B3,3") (pintype "passive"))
    )
    (net (code "152") (name "unconnected-(H2-MOUNT-PadB3,3)") (class "Default")
      (node (ref "H2") (pin "B3,3") (pinfunction "MOUNT_B3,3") (pintype "passive"))
    )
    (net (code "153") (name "unconnected-(H3-MOUNT-PadB3,3)") (class "Default")
      (node (ref "H3") (pin "B3,3") (pinfunction "MOUNT_B3,3") (pintype "passive"))
    )
    (net (code "154") (name "unconnected-(H4-MOUNT-PadB3,3)") (class "Default")
      (node (ref "H4") (pin "B3,3") (pinfunction "MOUNT_B3,3") (pintype "passive"))
    )
    (net (code "155") (name "unconnected-(U$1-PadBOOT0)") (class "Default")
      (node (ref "U$1") (pin "BOOT0") (pinfunction "BOOT0_BOOT0") (pintype "bidirectional"))
    )
    (net (code "156") (name "unconnected-(U$1-PadIOREF2)") (class "Default")
      (node (ref "U$1") (pin "IOREF2") (pinfunction "IOREF2_IOREF2") (pintype "input"))
    )
    (net (code "157") (name "unconnected-(U$1-PadNC1-PF7)") (class "Default")
      (node (ref "U$1") (pin "NC1-PF7") (pinfunction "NC1-PF7_NC1-PF7") (pintype "bidirectional"))
    )
    (net (code "158") (name "unconnected-(U$1-PadNC2-PF6)") (class "Default")
      (node (ref "U$1") (pin "NC2-PF6") (pinfunction "NC2-PF6_NC2-PF6") (pintype "bidirectional"))
    )
    (net (code "159") (name "unconnected-(U$1-PadNC3)") (class "Default")
      (node (ref "U$1") (pin "NC3") (pinfunction "NC3_NC3") (pintype "no_connect"))
    )
    (net (code "160") (name "unconnected-(U$1-PadNC4)") (class "Default")
      (node (ref "U$1") (pin "NC4") (pinfunction "NC4_NC4") (pintype "no_connect"))
    )
    (net (code "161") (name "unconnected-(U$1-PadNC5-PD8)") (class "Default")
      (node (ref "U$1") (pin "NC5-PD8") (pinfunction "NC5-PD8_NC5-PD8") (pintype "bidirectional"))
    )
    (net (code "162") (name "unconnected-(U$1-PadNC6-PB11)") (class "Default")
      (node (ref "U$1") (pin "NC6-PB11") (pinfunction "NC6-PB11_NC6-PB11") (pintype "no_connect"))
    )
    (net (code "163") (name "unconnected-(U$1-PadNC7-PF5)") (class "Default")
      (node (ref "U$1") (pin "NC7-PF5") (pinfunction "NC7-PF5_NC7-PF5") (pintype "bidirectional"))
    )
    (net (code "164") (name "unconnected-(U$1-PadNC8-PF4)") (class "Default")
      (node (ref "U$1") (pin "NC8-PF4") (pinfunction "NC8-PF4_NC8-PF4") (pintype "bidirectional"))
    )
    (net (code "165") (name "unconnected-(U$1-PadNRESET)") (class "Default")
      (node (ref "U$1") (pin "NRESET") (pinfunction "NRESET_NRESET") (pintype "input"))
    )
    (net (code "166") (name "unconnected-(U$1-PadPA1)") (class "Default")
      (node (ref "U$1") (pin "PA1") (pinfunction "PA1_PA1") (pintype "bidirectional"))
    )
    (net (code "167") (name "unconnected-(U$1-PadPA2)") (class "Default")
      (node (ref "U$1") (pin "PA2") (pinfunction "PA2_PA2") (pintype "bidirectional"))
    )
    (net (code "168") (name "unconnected-(U$1-PadPA3)") (class "Default")
      (node (ref "U$1") (pin "PA3") (pinfunction "PA3_PA3") (pintype "bidirectional"))
    )
    (net (code "169") (name "unconnected-(U$1-PadPA5)") (class "Default")
      (node (ref "U$1") (pin "PA5") (pinfunction "PA5_PA5") (pintype "bidirectional"))
    )
    (net (code "170") (name "unconnected-(U$1-PadPA7)") (class "Default")
      (node (ref "U$1") (pin "PA7") (pinfunction "PA7_PA7") (pintype "bidirectional"))
    )
    (net (code "171") (name "unconnected-(U$1-PadPA9)") (class "Default")
      (node (ref "U$1") (pin "PA9") (pinfunction "PA9_PA9") (pintype "bidirectional"))
    )
    (net (code "172") (name "unconnected-(U$1-PadPA10)") (class "Default")
      (node (ref "U$1") (pin "PA10") (pinfunction "PA10_PA10") (pintype "bidirectional"))
    )
    (net (code "173") (name "unconnected-(U$1-PadPA11)") (class "Default")
      (node (ref "U$1") (pin "PA11") (pinfunction "PA11_PA11") (pintype "bidirectional"))
    )
    (net (code "174") (name "unconnected-(U$1-PadPA12)") (class "Default")
      (node (ref "U$1") (pin "PA12") (pinfunction "PA12_PA12") (pintype "bidirectional"))
    )
    (net (code "175") (name "unconnected-(U$1-PadPA13)") (class "Default")
      (node (ref "U$1") (pin "PA13") (pinfunction "PA13_PA13") (pintype "bidirectional"))
    )
    (net (code "176") (name "unconnected-(U$1-PadPA14)") (class "Default")
      (node (ref "U$1") (pin "PA14") (pinfunction "PA14_PA14") (pintype "bidirectional"))
    )
    (net (code "177") (name "unconnected-(U$1-PadPB0)") (class "Default")
      (node (ref "U$1") (pin "PB0") (pinfunction "PB0_PB0") (pintype "bidirectional"))
    )
    (net (code "178") (name "unconnected-(U$1-PadPB13)") (class "Default")
      (node (ref "U$1") (pin "PB13") (pinfunction "PB13_PB13") (pintype "bidirectional"))
    )
    (net (code "179") (name "unconnected-(U$1-PadPC1)") (class "Default")
      (node (ref "U$1") (pin "PC1") (pinfunction "PC1_PC1") (pintype "bidirectional"))
    )
    (net (code "180") (name "unconnected-(U$1-PadPC4)") (class "Default")
      (node (ref "U$1") (pin "PC4") (pinfunction "PC4_PC4") (pintype "bidirectional"))
    )
    (net (code "181") (name "unconnected-(U$1-PadPC5)") (class "Default")
      (node (ref "U$1") (pin "PC5") (pinfunction "PC5_PC5") (pintype "bidirectional"))
    )
    (net (code "182") (name "unconnected-(U$1-PadPC13)") (class "Default")
      (node (ref "U$1") (pin "PC13") (pinfunction "PC13_PC13") (pintype "bidirectional"))
    )
    (net (code "183") (name "unconnected-(U$1-PadPC14)") (class "Default")
      (node (ref "U$1") (pin "PC14") (pinfunction "PC14_PC14") (pintype "bidirectional"))
    )
    (net (code "184") (name "unconnected-(U$1-PadPC15)") (class "Default")
      (node (ref "U$1") (pin "PC15") (pinfunction "PC15_PC15") (pintype "bidirectional"))
    )
    (net (code "185") (name "unconnected-(U$1-PadPF0-PH0)") (class "Default")
      (node (ref "U$1") (pin "PF0-PH0") (pinfunction "PF0-PH0_PF0-PH0") (pintype "bidirectional"))
    )
  )
)
